# io-board-f-8.net
KiCad netlist of a schematic drawn in EAGLE
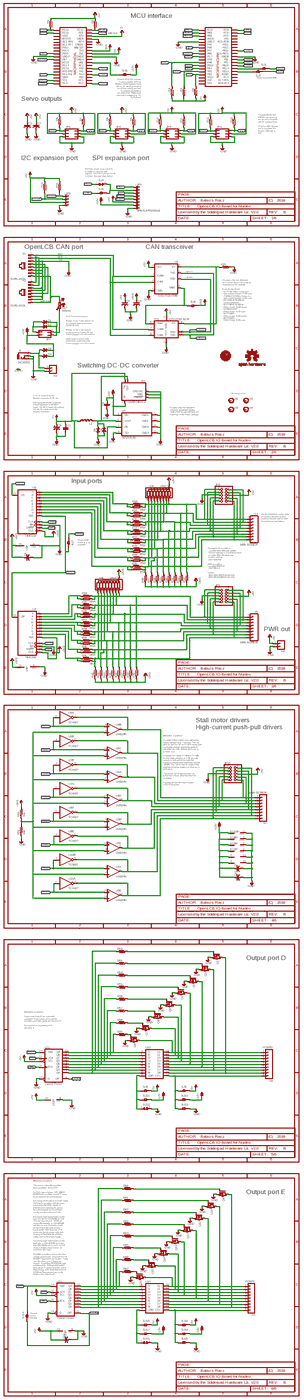
[diagram p0: schematic, sheet 1, overview]
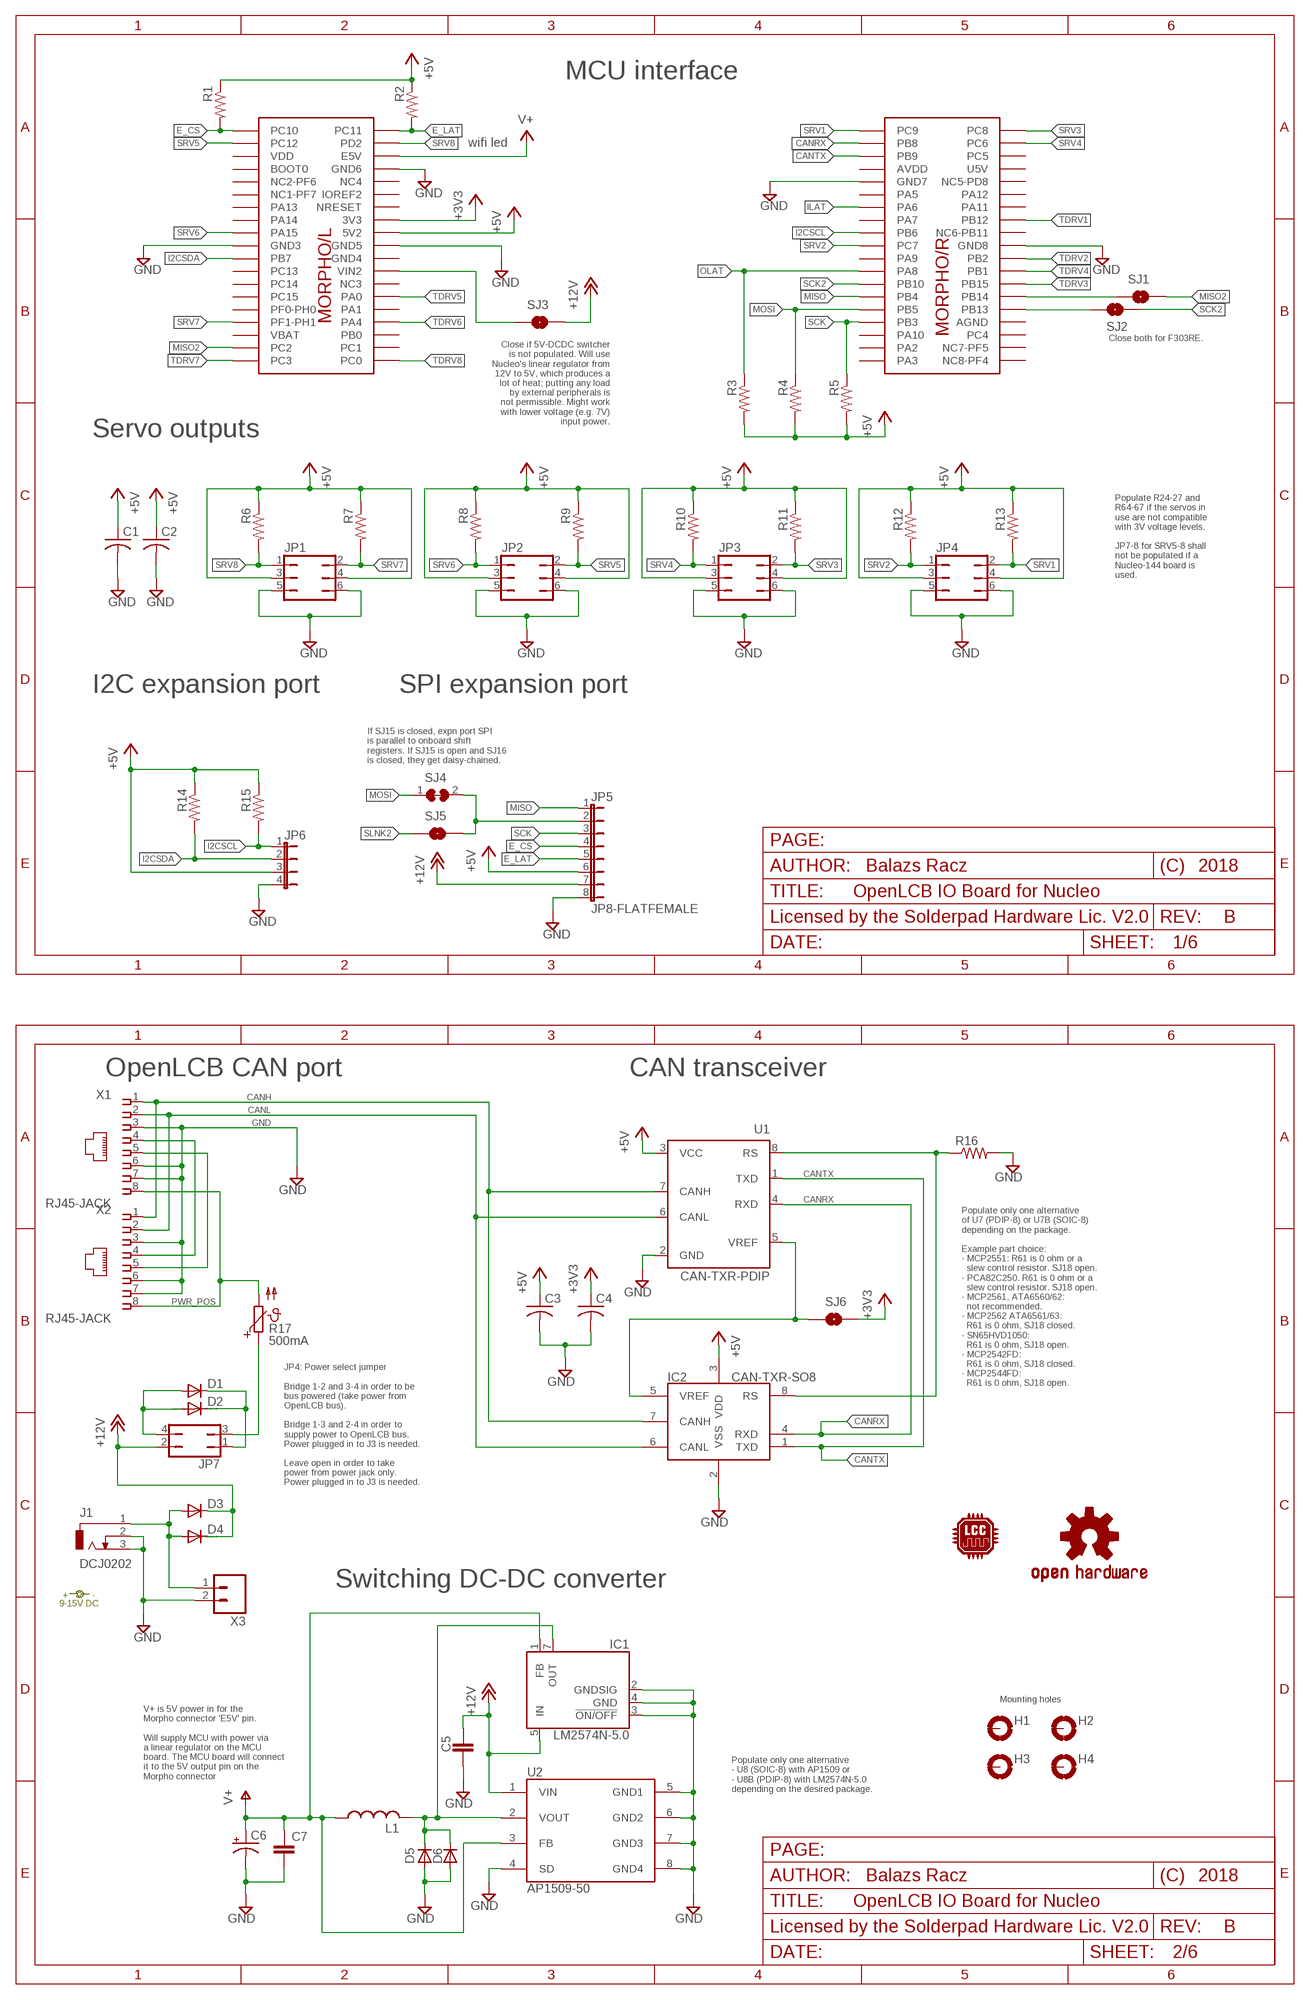
[diagram p1: schematic, sheet 1, part 1 of 4]
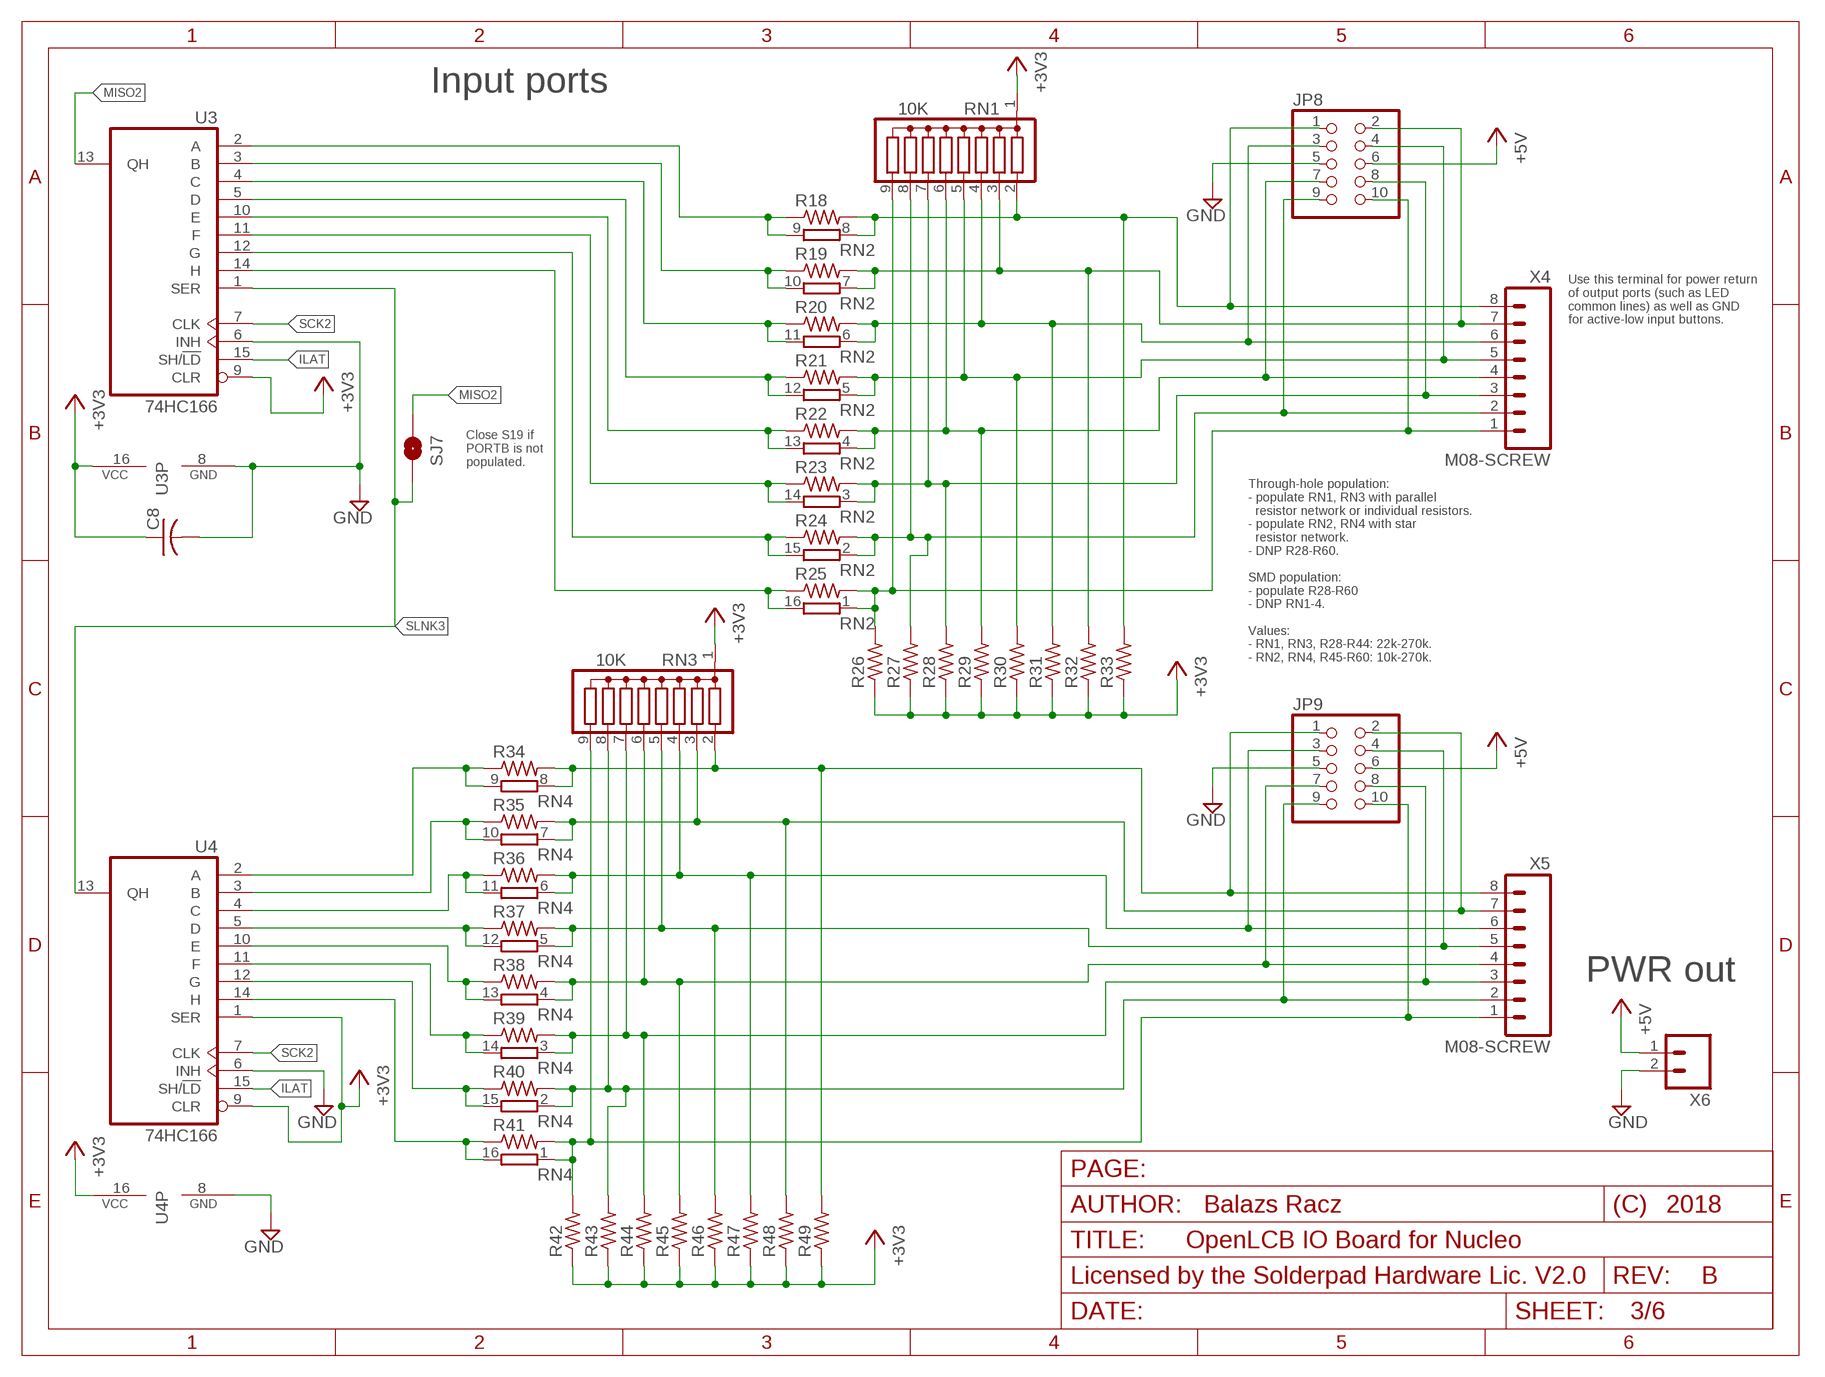
[diagram p2: schematic, sheet 1, part 2 of 4]
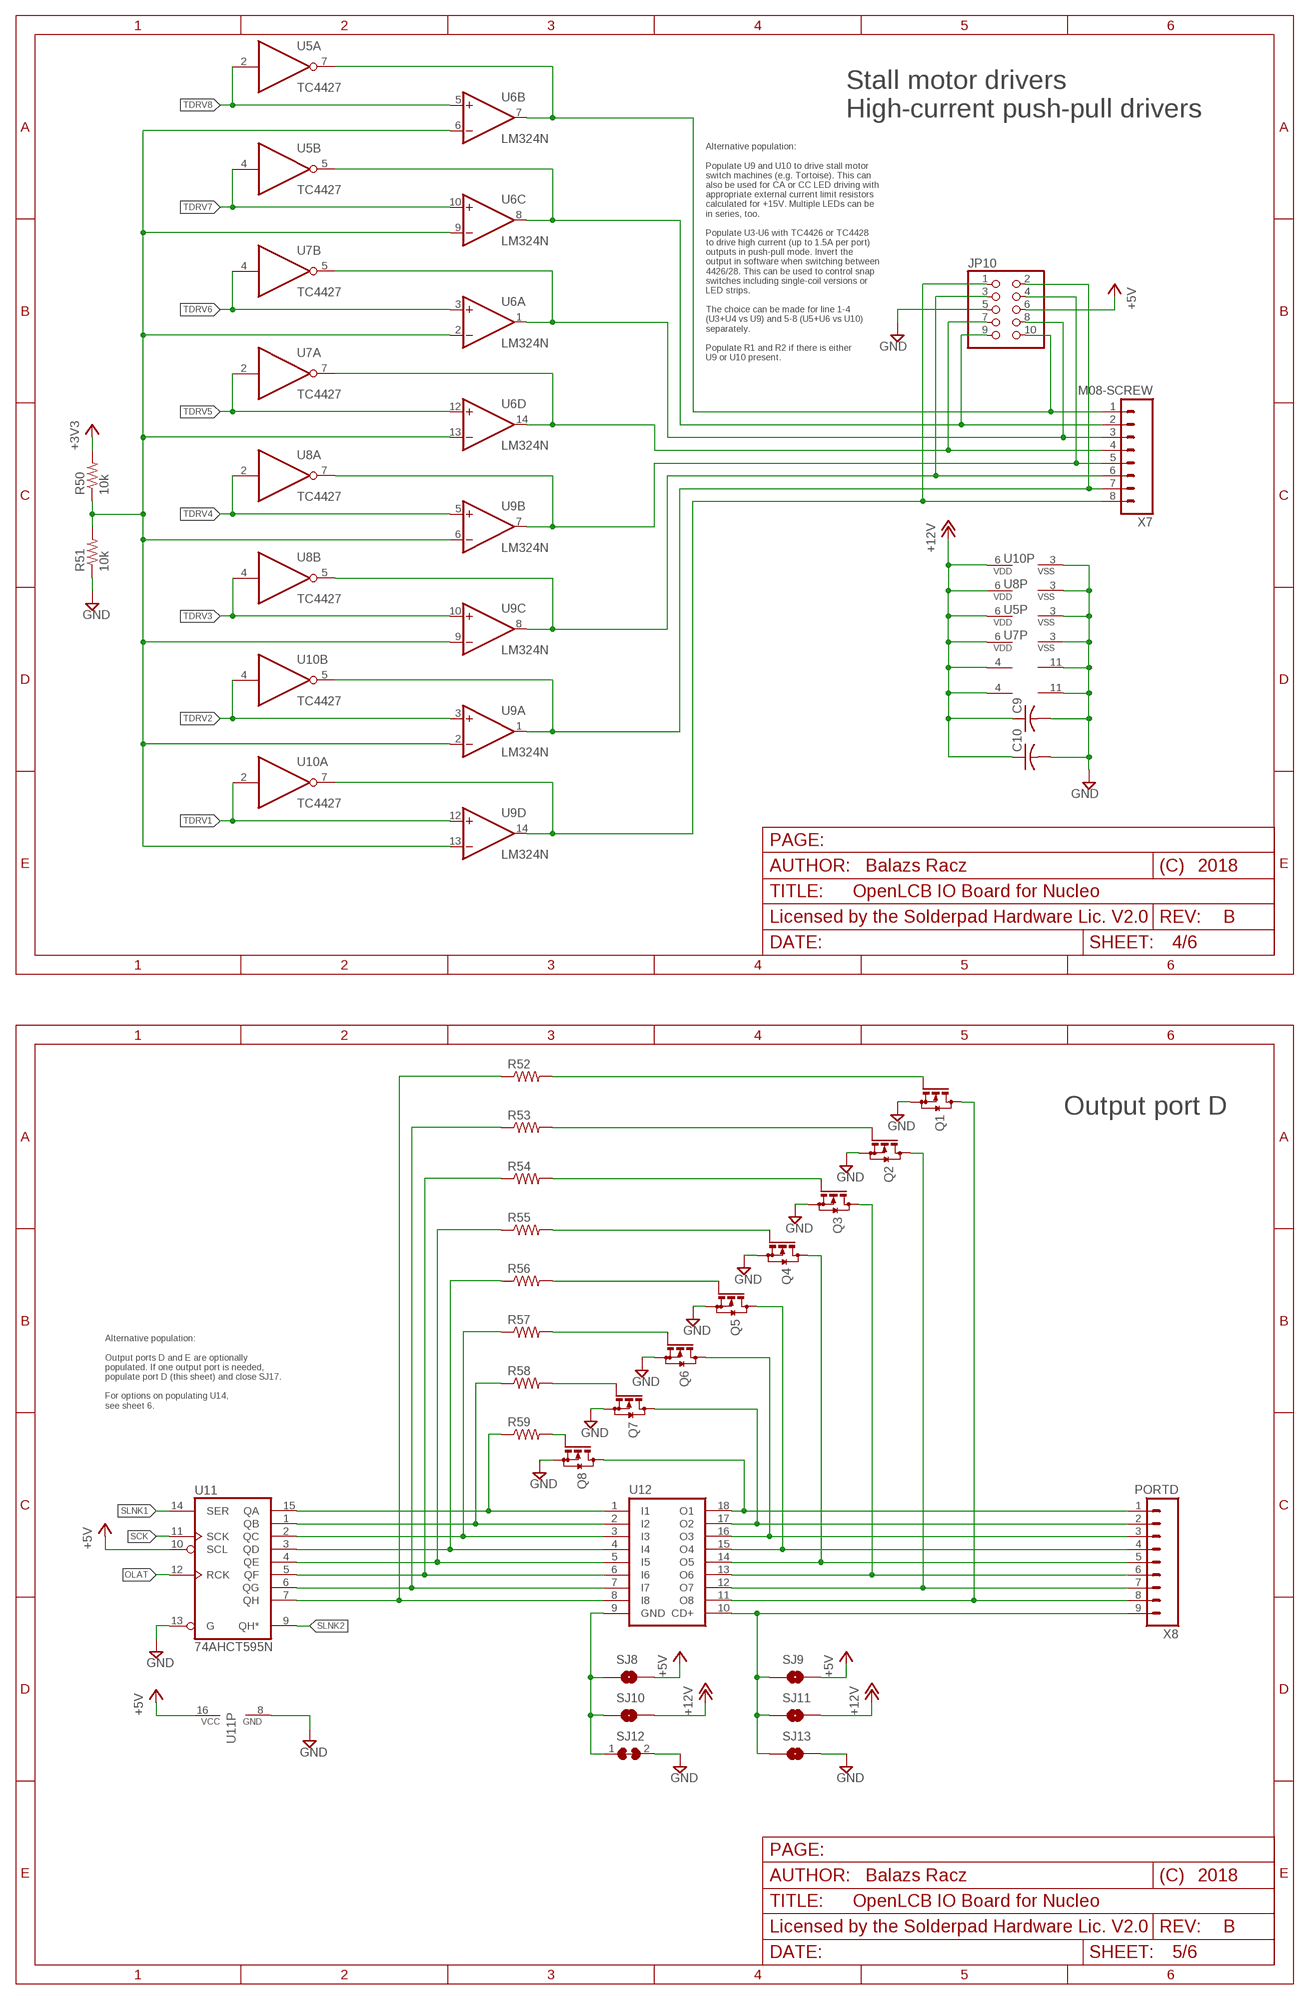
[diagram p3: schematic, sheet 1, part 3 of 4]
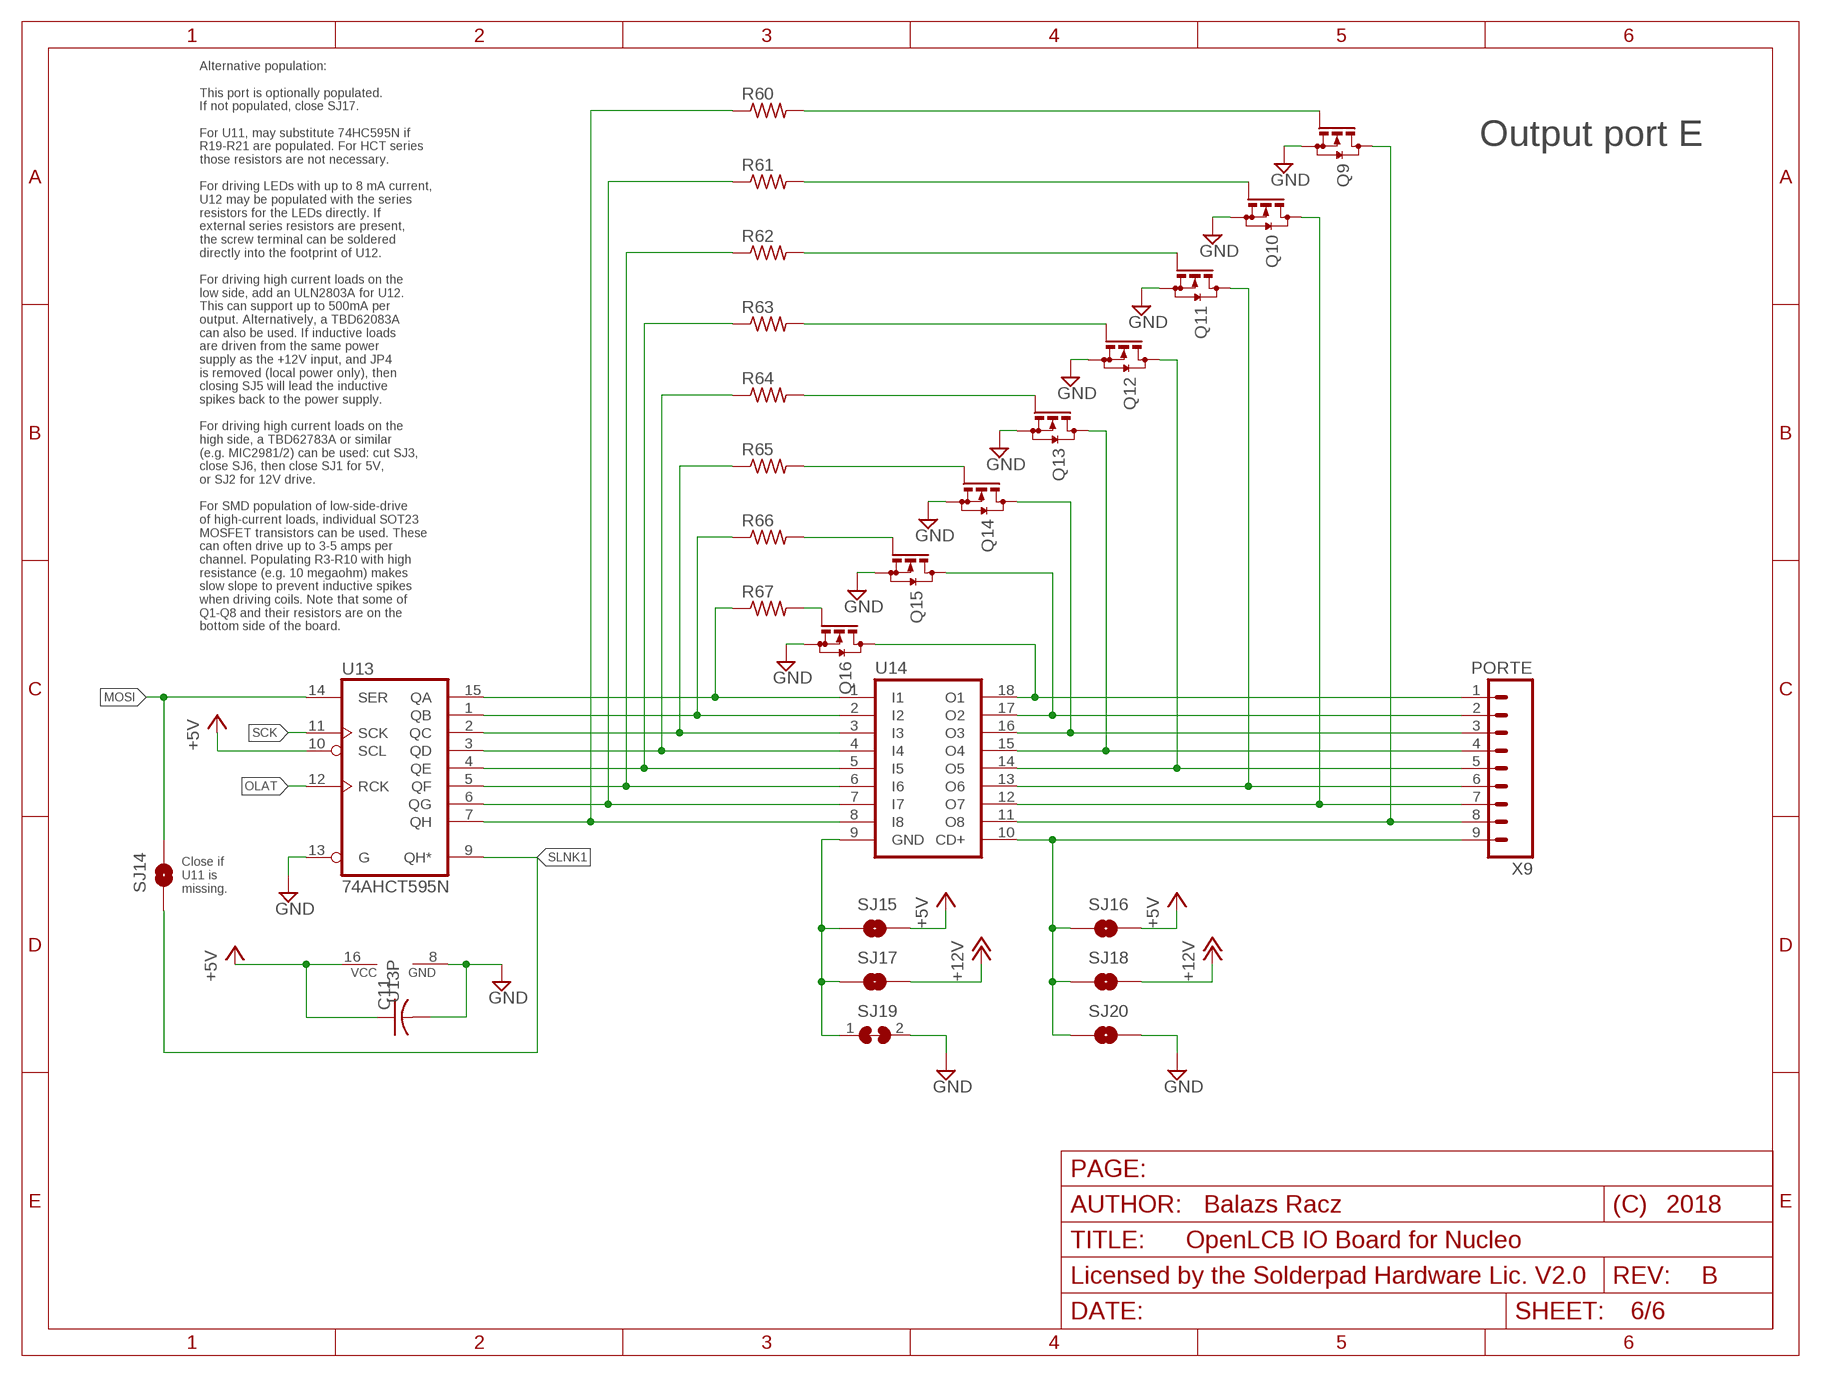
[diagram p4: schematic, sheet 1, part 4 of 4]

(export (version "E")
  (design (tool "Eeschema 10.0.6"))
  (components
    (comp (ref "C1")
      (value "C-USC1206")
      (footprint "eagle-import:C1206")
      (libsource (lib "eagle-import") (part "C-USC1206"))
    )
    (comp (ref "C2")
      (value "C-USC1206")
      (footprint "eagle-import:C1206")
      (libsource (lib "eagle-import") (part "C-USC1206"))
    )
    (comp (ref "C3")
      (value "C-USC0805")
      (footprint "eagle-import:C0805")
      (libsource (lib "eagle-import") (part "C-USC0805"))
    )
    (comp (ref "C4")
      (value "C-USC0805")
      (footprint "eagle-import:C0805")
      (libsource (lib "eagle-import") (part "C-USC0805"))
    )
    (comp (ref "C5")
      (value "C-EUC1206")
      (footprint "eagle-import:C1206")
      (libsource (lib "eagle-import") (part "C-EUC1206"))
    )
    (comp (ref "C6")
      (value "CPOL-USE2.5-5")
      (footprint "eagle-import:E2,5-5")
      (libsource (lib "eagle-import") (part "CPOL-USE2.5-5"))
    )
    (comp (ref "C7")
      (value "C-EUC1206")
      (footprint "eagle-import:C1206")
      (libsource (lib "eagle-import") (part "C-EUC1206"))
    )
    (comp (ref "C8")
      (value "C-USC0805")
      (footprint "eagle-import:C0805")
      (libsource (lib "eagle-import") (part "C-USC0805"))
    )
    (comp (ref "C9")
      (value "C-USC1206")
      (footprint "eagle-import:C1206")
      (libsource (lib "eagle-import") (part "C-USC1206"))
    )
    (comp (ref "C10")
      (value "C-USC1206")
      (footprint "eagle-import:C1206")
      (libsource (lib "eagle-import") (part "C-USC1206"))
    )
    (comp (ref "C11")
      (value "C-USC0805")
      (footprint "eagle-import:C0805")
      (libsource (lib "eagle-import") (part "C-USC0805"))
    )
    (comp (ref "D1")
      (value "DIODEDO-214AA-NODOC")
      (footprint "eagle-import:DO214AA-NODOC")
      (libsource (lib "eagle-import") (part "DIODEDO-214AA-NODOC"))
    )
    (comp (ref "D2")
      (value "DIODE-DO41-7.6")
      (footprint "eagle-import:DO41-7.6")
      (libsource (lib "eagle-import") (part "DIODE-DO41-7.6"))
    )
    (comp (ref "D3")
      (value "DIODEDO-214AA-NODOC")
      (footprint "eagle-import:DO214AA-NODOC")
      (libsource (lib "eagle-import") (part "DIODEDO-214AA-NODOC"))
    )
    (comp (ref "D4")
      (value "DIODE-DO41-7.6")
      (footprint "eagle-import:DO41-7.6")
      (libsource (lib "eagle-import") (part "DIODE-DO41-7.6"))
    )
    (comp (ref "D5")
      (value "DIODE-DO41-7.6")
      (footprint "eagle-import:DO41-7.6")
      (libsource (lib "eagle-import") (part "DIODE-DO41-7.6"))
    )
    (comp (ref "D6")
      (value "DIODEDO-214AA-NODOC")
      (footprint "eagle-import:DO214AA-NODOC")
      (libsource (lib "eagle-import") (part "DIODEDO-214AA-NODOC"))
    )
    (comp (ref "G1")
      (value "NUCLEO_64_GENERIC")
      (footprint "eagle-import:NUCLEO_BRD_BASE64")
      (libsource (lib "eagle-import") (part "NUCLEO_64_GENERIC"))
    )
    (comp (ref "H1")
      (value "MOUNT-PAD-ROUND3.3")
      (footprint "eagle-import:3,3-PAD")
      (libsource (lib "eagle-import") (part "MOUNT-PAD-ROUND3.3"))
    )
    (comp (ref "H2")
      (value "MOUNT-PAD-ROUND3.3")
      (footprint "eagle-import:3,3-PAD")
      (libsource (lib "eagle-import") (part "MOUNT-PAD-ROUND3.3"))
    )
    (comp (ref "H3")
      (value "MOUNT-PAD-ROUND3.3")
      (footprint "eagle-import:3,3-PAD")
      (libsource (lib "eagle-import") (part "MOUNT-PAD-ROUND3.3"))
    )
    (comp (ref "H4")
      (value "MOUNT-PAD-ROUND3.3")
      (footprint "eagle-import:3,3-PAD")
      (libsource (lib "eagle-import") (part "MOUNT-PAD-ROUND3.3"))
    )
    (comp (ref "IC1")
      (value "LM2574N-5.0")
      (footprint "eagle-import:DIL08")
      (libsource (lib "eagle-import") (part "LM2574?-N5.0"))
    )
    (comp (ref "IC2")
      (value "CAN-TXR-SO8")
      (footprint "eagle-import:SO-08")
      (libsource (lib "eagle-import") (part "MCP2551-SN"))
    )
    (comp (ref "J1")
      (value "DCJ0202")
      (footprint "eagle-import:DCJ0202")
      (libsource (lib "eagle-import") (part "DCJ0202"))
    )
    (comp (ref "JP1")
      (value "JP3Q")
      (footprint "eagle-import:JP3Q")
      (libsource (lib "eagle-import") (part "JP3Q"))
    )
    (comp (ref "JP2")
      (value "JP3Q")
      (footprint "eagle-import:JP3Q")
      (libsource (lib "eagle-import") (part "JP3Q"))
    )
    (comp (ref "JP3")
      (value "JP3Q")
      (footprint "eagle-import:JP3Q")
      (libsource (lib "eagle-import") (part "JP3Q"))
    )
    (comp (ref "JP4")
      (value "JP3Q")
      (footprint "eagle-import:JP3Q")
      (libsource (lib "eagle-import") (part "JP3Q"))
    )
    (comp (ref "JP5")
      (value "JP8-FLATFEMALE")
      (footprint "eagle-import:JP8F-FEM")
      (libsource (lib "eagle-import") (part "JP8-FLATFEMALE"))
    )
    (comp (ref "JP6")
      (value "JP4-FLAT")
      (footprint "eagle-import:JP4F")
      (libsource (lib "eagle-import") (part "JP4-FLAT"))
    )
    (comp (ref "JP7")
      (value "JP2Q")
      (footprint "eagle-import:JP2Q")
      (libsource (lib "eagle-import") (part "JP2Q"))
    )
    (comp (ref "JP8")
      (value "PINHD-2X5CN")
      (footprint "eagle-import:CON10M")
      (libsource (lib "eagle-import") (part "PINHD-2X5CN"))
    )
    (comp (ref "JP9")
      (value "PINHD-2X5CN")
      (footprint "eagle-import:CON10M")
      (libsource (lib "eagle-import") (part "PINHD-2X5CN"))
    )
    (comp (ref "JP10")
      (value "PINHD-2X5CN")
      (footprint "eagle-import:CON10M")
      (libsource (lib "eagle-import") (part "PINHD-2X5CN"))
    )
    (comp (ref "L1")
      (value "L-US")
      (footprint "eagle-import:L5-8,5")
      (libsource (lib "eagle-import") (part "L-US"))
    )
    (comp (ref "LG1")
      (value "LCC_LOGO")
      (footprint "eagle-import:LCC_LOGO")
      (libsource (lib "eagle-import") (part "LCC_LOGO"))
    )
    (comp (ref "LOGO1")
      (value "DOC-OSHW-LOGOM")
      (footprint "eagle-import:OSHW-LOGO-M")
      (libsource (lib "eagle-import") (part "DOC-OSHW-LOGOM"))
    )
    (comp (ref "P1")
      (value "9-15V DC")
      (footprint "eagle-import:POWER_USAGE")
      (libsource (lib "eagle-import") (part "DOC-POWER_LABEL"))
    )
    (comp (ref "Q1")
      (value "BSS123")
      (footprint "eagle-import:SOT23")
      (libsource (lib "eagle-import") (part "BSS123"))
    )
    (comp (ref "Q2")
      (value "BSS123")
      (footprint "eagle-import:SOT23")
      (libsource (lib "eagle-import") (part "BSS123"))
    )
    (comp (ref "Q3")
      (value "BSS123")
      (footprint "eagle-import:SOT23")
      (libsource (lib "eagle-import") (part "BSS123"))
    )
    (comp (ref "Q4")
      (value "BSS123")
      (footprint "eagle-import:SOT23")
      (libsource (lib "eagle-import") (part "BSS123"))
    )
    (comp (ref "Q5")
      (value "BSS123")
      (footprint "eagle-import:SOT23")
      (libsource (lib "eagle-import") (part "BSS123"))
    )
    (comp (ref "Q6")
      (value "BSS123")
      (footprint "eagle-import:SOT23")
      (libsource (lib "eagle-import") (part "BSS123"))
    )
    (comp (ref "Q7")
      (value "BSS123")
      (footprint "eagle-import:SOT23")
      (libsource (lib "eagle-import") (part "BSS123"))
    )
    (comp (ref "Q8")
      (value "BSS123")
      (footprint "eagle-import:SOT23")
      (libsource (lib "eagle-import") (part "BSS123"))
    )
    (comp (ref "Q9")
      (value "BSS123")
      (footprint "eagle-import:SOT23")
      (libsource (lib "eagle-import") (part "BSS123"))
    )
    (comp (ref "Q10")
      (value "BSS123")
      (footprint "eagle-import:SOT23")
      (libsource (lib "eagle-import") (part "BSS123"))
    )
    (comp (ref "Q11")
      (value "BSS123")
      (footprint "eagle-import:SOT23")
      (libsource (lib "eagle-import") (part "BSS123"))
    )
    (comp (ref "Q12")
      (value "BSS123")
      (footprint "eagle-import:SOT23")
      (libsource (lib "eagle-import") (part "BSS123"))
    )
    (comp (ref "Q13")
      (value "BSS123")
      (footprint "eagle-import:SOT23")
      (libsource (lib "eagle-import") (part "BSS123"))
    )
    (comp (ref "Q14")
      (value "BSS123")
      (footprint "eagle-import:SOT23")
      (libsource (lib "eagle-import") (part "BSS123"))
    )
    (comp (ref "Q15")
      (value "BSS123")
      (footprint "eagle-import:SOT23")
      (libsource (lib "eagle-import") (part "BSS123"))
    )
    (comp (ref "Q16")
      (value "BSS123")
      (footprint "eagle-import:SOT23")
      (libsource (lib "eagle-import") (part "BSS123"))
    )
    (comp (ref "R1")
      (value "R-US_R0805")
      (footprint "eagle-import:R0805")
      (libsource (lib "eagle-import") (part "rcl_334_R-US_R0805"))
    )
    (comp (ref "R2")
      (value "R-US_R0805")
      (footprint "eagle-import:R0805")
      (libsource (lib "eagle-import") (part "rcl_334_R-US_R0805"))
    )
    (comp (ref "R3")
      (value "R-US_R0805")
      (footprint "eagle-import:R0805")
      (libsource (lib "eagle-import") (part "rcl_334_R-US_R0805"))
    )
    (comp (ref "R4")
      (value "R-US_R0805")
      (footprint "eagle-import:R0805")
      (libsource (lib "eagle-import") (part "rcl_334_R-US_R0805"))
    )
    (comp (ref "R5")
      (value "R-US_R0805")
      (footprint "eagle-import:R0805")
      (libsource (lib "eagle-import") (part "rcl_334_R-US_R0805"))
    )
    (comp (ref "R6")
      (value "R-US_R0805")
      (footprint "eagle-import:R0805")
      (libsource (lib "eagle-import") (part "rcl_334_R-US_R0805"))
    )
    (comp (ref "R7")
      (value "R-US_R0805")
      (footprint "eagle-import:R0805")
      (libsource (lib "eagle-import") (part "rcl_334_R-US_R0805"))
    )
    (comp (ref "R8")
      (value "R-US_R0805")
      (footprint "eagle-import:R0805")
      (libsource (lib "eagle-import") (part "rcl_334_R-US_R0805"))
    )
    (comp (ref "R9")
      (value "R-US_R0805")
      (footprint "eagle-import:R0805")
      (libsource (lib "eagle-import") (part "rcl_334_R-US_R0805"))
    )
    (comp (ref "R10")
      (value "R-US_R0805")
      (footprint "eagle-import:R0805")
      (libsource (lib "eagle-import") (part "rcl_334_R-US_R0805"))
    )
    (comp (ref "R11")
      (value "R-US_R0805")
      (footprint "eagle-import:R0805")
      (libsource (lib "eagle-import") (part "rcl_334_R-US_R0805"))
    )
    (comp (ref "R12")
      (value "R-US_R0805")
      (footprint "eagle-import:R0805")
      (libsource (lib "eagle-import") (part "rcl_334_R-US_R0805"))
    )
    (comp (ref "R13")
      (value "R-US_R0805")
      (footprint "eagle-import:R0805")
      (libsource (lib "eagle-import") (part "rcl_334_R-US_R0805"))
    )
    (comp (ref "R14")
      (value "R-US_R0805")
      (footprint "eagle-import:R0805")
      (libsource (lib "eagle-import") (part "rcl_334_R-US_R0805"))
    )
    (comp (ref "R15")
      (value "R-US_R0805")
      (footprint "eagle-import:R0805")
      (libsource (lib "eagle-import") (part "rcl_334_R-US_R0805"))
    )
    (comp (ref "R16")
      (value "R-US_R0805")
      (footprint "eagle-import:R0805")
      (libsource (lib "eagle-import") (part "rcl_334_R-US_R0805"))
    )
    (comp (ref "R17")
      (value "500mA")
      (footprint "eagle-import:PTC1812")
      (libsource (lib "eagle-import") (part "PTC_1812"))
    )
    (comp (ref "R18")
      (value "R-US_R0603")
      (footprint "eagle-import:R0603")
      (libsource (lib "eagle-import") (part "rcl_334_R-US_R0603"))
    )
    (comp (ref "R19")
      (value "R-US_R0603")
      (footprint "eagle-import:R0603")
      (libsource (lib "eagle-import") (part "rcl_334_R-US_R0603"))
    )
    (comp (ref "R20")
      (value "R-US_R0603")
      (footprint "eagle-import:R0603")
      (libsource (lib "eagle-import") (part "rcl_334_R-US_R0603"))
    )
    (comp (ref "R21")
      (value "R-US_R0603")
      (footprint "eagle-import:R0603")
      (libsource (lib "eagle-import") (part "rcl_334_R-US_R0603"))
    )
    (comp (ref "R22")
      (value "R-US_R0603")
      (footprint "eagle-import:R0603")
      (libsource (lib "eagle-import") (part "rcl_334_R-US_R0603"))
    )
    (comp (ref "R23")
      (value "R-US_R0603")
      (footprint "eagle-import:R0603")
      (libsource (lib "eagle-import") (part "rcl_334_R-US_R0603"))
    )
    (comp (ref "R24")
      (value "R-US_R0603")
      (footprint "eagle-import:R0603")
      (libsource (lib "eagle-import") (part "rcl_334_R-US_R0603"))
    )
    (comp (ref "R25")
      (value "R-US_R0603")
      (footprint "eagle-import:R0603")
      (libsource (lib "eagle-import") (part "rcl_334_R-US_R0603"))
    )
    (comp (ref "R26")
      (value "R-US")
      (footprint "eagle-import:R0603")
      (libsource (lib "eagle-import") (part "R-US"))
    )
    (comp (ref "R27")
      (value "R-US")
      (footprint "eagle-import:R0603")
      (libsource (lib "eagle-import") (part "R-US"))
    )
    (comp (ref "R28")
      (value "R-US")
      (footprint "eagle-import:R0603")
      (libsource (lib "eagle-import") (part "R-US"))
    )
    (comp (ref "R29")
      (value "R-US")
      (footprint "eagle-import:R0603")
      (libsource (lib "eagle-import") (part "R-US"))
    )
    (comp (ref "R30")
      (value "R-US")
      (footprint "eagle-import:R0603")
      (libsource (lib "eagle-import") (part "R-US"))
    )
    (comp (ref "R31")
      (value "R-US")
      (footprint "eagle-import:R0603")
      (libsource (lib "eagle-import") (part "R-US"))
    )
    (comp (ref "R32")
      (value "R-US")
      (footprint "eagle-import:R0603")
      (libsource (lib "eagle-import") (part "R-US"))
    )
    (comp (ref "R33")
      (value "R-US")
      (footprint "eagle-import:R0603")
      (libsource (lib "eagle-import") (part "R-US"))
    )
    (comp (ref "R34")
      (value "R-US_R0603")
      (footprint "eagle-import:R0603")
      (libsource (lib "eagle-import") (part "rcl_334_R-US_R0603"))
    )
    (comp (ref "R35")
      (value "R-US_R0603")
      (footprint "eagle-import:R0603")
      (libsource (lib "eagle-import") (part "rcl_334_R-US_R0603"))
    )
    (comp (ref "R36")
      (value "R-US_R0603")
      (footprint "eagle-import:R0603")
      (libsource (lib "eagle-import") (part "rcl_334_R-US_R0603"))
    )
    (comp (ref "R37")
      (value "R-US_R0603")
      (footprint "eagle-import:R0603")
      (libsource (lib "eagle-import") (part "rcl_334_R-US_R0603"))
    )
    (comp (ref "R38")
      (value "R-US_R0603")
      (footprint "eagle-import:R0603")
      (libsource (lib "eagle-import") (part "rcl_334_R-US_R0603"))
    )
    (comp (ref "R39")
      (value "R-US_R0603")
      (footprint "eagle-import:R0603")
      (libsource (lib "eagle-import") (part "rcl_334_R-US_R0603"))
    )
    (comp (ref "R40")
      (value "R-US_R0603")
      (footprint "eagle-import:R0603")
      (libsource (lib "eagle-import") (part "rcl_334_R-US_R0603"))
    )
    (comp (ref "R41")
      (value "R-US_R0603")
      (footprint "eagle-import:R0603")
      (libsource (lib "eagle-import") (part "rcl_334_R-US_R0603"))
    )
    (comp (ref "R42")
      (value "R-US")
      (footprint "eagle-import:R0603")
      (libsource (lib "eagle-import") (part "R-US"))
    )
    (comp (ref "R43")
      (value "R-US")
      (footprint "eagle-import:R0603")
      (libsource (lib "eagle-import") (part "R-US"))
    )
    (comp (ref "R44")
      (value "R-US")
      (footprint "eagle-import:R0603")
      (libsource (lib "eagle-import") (part "R-US"))
    )
    (comp (ref "R45")
      (value "R-US")
      (footprint "eagle-import:R0603")
      (libsource (lib "eagle-import") (part "R-US"))
    )
    (comp (ref "R46")
      (value "R-US")
      (footprint "eagle-import:R0603")
      (libsource (lib "eagle-import") (part "R-US"))
    )
    (comp (ref "R47")
      (value "R-US")
      (footprint "eagle-import:R0603")
      (libsource (lib "eagle-import") (part "R-US"))
    )
    (comp (ref "R48")
      (value "R-US")
      (footprint "eagle-import:R0603")
      (libsource (lib "eagle-import") (part "R-US"))
    )
    (comp (ref "R49")
      (value "R-US")
      (footprint "eagle-import:R0603")
      (libsource (lib "eagle-import") (part "R-US"))
    )
    (comp (ref "R50")
      (value "10k")
      (footprint "eagle-import:R0805")
      (libsource (lib "eagle-import") (part "R-US_R0805"))
    )
    (comp (ref "R51")
      (value "10k")
      (footprint "eagle-import:R0805")
      (libsource (lib "eagle-import") (part "R-US_R0805"))
    )
    (comp (ref "R52")
      (value "R-US_R0603")
      (footprint "eagle-import:R0603")
      (libsource (lib "eagle-import") (part "R-US_R0603"))
    )
    (comp (ref "R53")
      (value "R-US_R0603")
      (footprint "eagle-import:R0603")
      (libsource (lib "eagle-import") (part "R-US_R0603"))
    )
    (comp (ref "R54")
      (value "R-US_R0603")
      (footprint "eagle-import:R0603")
      (libsource (lib "eagle-import") (part "R-US_R0603"))
    )
    (comp (ref "R55")
      (value "R-US_R0603")
      (footprint "eagle-import:R0603")
      (libsource (lib "eagle-import") (part "R-US_R0603"))
    )
    (comp (ref "R56")
      (value "R-US_R0603")
      (footprint "eagle-import:R0603")
      (libsource (lib "eagle-import") (part "R-US_R0603"))
    )
    (comp (ref "R57")
      (value "R-US_R0603")
      (footprint "eagle-import:R0603")
      (libsource (lib "eagle-import") (part "R-US_R0603"))
    )
    (comp (ref "R58")
      (value "R-US_R0603")
      (footprint "eagle-import:R0603")
      (libsource (lib "eagle-import") (part "R-US_R0603"))
    )
    (comp (ref "R59")
      (value "R-US_R0603")
      (footprint "eagle-import:R0603")
      (libsource (lib "eagle-import") (part "R-US_R0603"))
    )
    (comp (ref "R60")
      (value "R-US_R0603")
      (footprint "eagle-import:R0603")
      (libsource (lib "eagle-import") (part "R-US_R0603"))
    )
    (comp (ref "R61")
      (value "R-US_R0603")
      (footprint "eagle-import:R0603")
      (libsource (lib "eagle-import") (part "R-US_R0603"))
    )
    (comp (ref "R62")
      (value "R-US_R0603")
      (footprint "eagle-import:R0603")
      (libsource (lib "eagle-import") (part "R-US_R0603"))
    )
    (comp (ref "R63")
      (value "R-US_R0603")
      (footprint "eagle-import:R0603")
      (libsource (lib "eagle-import") (part "R-US_R0603"))
    )
    (comp (ref "R64")
      (value "R-US_R0603")
      (footprint "eagle-import:R0603")
      (libsource (lib "eagle-import") (part "R-US_R0603"))
    )
    (comp (ref "R65")
      (value "R-US_R0603")
      (footprint "eagle-import:R0603")
      (libsource (lib "eagle-import") (part "R-US_R0603"))
    )
    (comp (ref "R66")
      (value "R-US_R0603")
      (footprint "eagle-import:R0603")
      (libsource (lib "eagle-import") (part "R-US_R0603"))
    )
    (comp (ref "R67")
      (value "R-US_R0603")
      (footprint "eagle-import:R0603")
      (libsource (lib "eagle-import") (part "R-US_R0603"))
    )
    (comp (ref "RN1")
      (value "10K")
      (footprint "eagle-import:SIL9")
      (libsource (lib "eagle-import") (part "G08R"))
    )
    (comp (ref "RN2")
      (value "8R-P")
      (footprint "eagle-import:DIL16")
      (libsource (lib "eagle-import") (part "8R-P"))
    )
    (comp (ref "RN3")
      (value "10K")
      (footprint "eagle-import:SIL9")
      (libsource (lib "eagle-import") (part "G08R"))
    )
    (comp (ref "RN4")
      (value "8R-P")
      (footprint "eagle-import:DIL16")
      (libsource (lib "eagle-import") (part "8R-P"))
    )
    (comp (ref "SJ1")
      (value "SJRND2")
      (footprint "eagle-import:SJ_RND2")
      (libsource (lib "eagle-import") (part "SJRND2"))
    )
    (comp (ref "SJ2")
      (value "SJRND2")
      (footprint "eagle-import:SJ_RND2")
      (libsource (lib "eagle-import") (part "SJRND2"))
    )
    (comp (ref "SJ3")
      (value "SJRND2")
      (footprint "eagle-import:SJ_RND2")
      (libsource (lib "eagle-import") (part "SJRND2"))
    )
    (comp (ref "SJ4")
      (value "SJ-C")
      (footprint "eagle-import:SJW-C")
      (libsource (lib "eagle-import") (part "SJ-C"))
    )
    (comp (ref "SJ5")
      (value "SJRND2")
      (footprint "eagle-import:SJ_RND2")
      (libsource (lib "eagle-import") (part "SJRND2"))
    )
    (comp (ref "SJ6")
      (value "SJRND2")
      (footprint "eagle-import:SJ_RND2")
      (libsource (lib "eagle-import") (part "SJRND2"))
    )
    (comp (ref "SJ7")
      (value "SJRND2")
      (footprint "eagle-import:SJ_RND2")
      (libsource (lib "eagle-import") (part "SJRND2"))
    )
    (comp (ref "SJ8")
      (value "SJRND2")
      (footprint "eagle-import:SJ_RND2")
      (libsource (lib "eagle-import") (part "SJRND2"))
    )
    (comp (ref "SJ9")
      (value "SJRND2")
      (footprint "eagle-import:SJ_RND2")
      (libsource (lib "eagle-import") (part "SJRND2"))
    )
    (comp (ref "SJ10")
      (value "SJRND2")
      (footprint "eagle-import:SJ_RND2")
      (libsource (lib "eagle-import") (part "SJRND2"))
    )
    (comp (ref "SJ11")
      (value "SJRND2")
      (footprint "eagle-import:SJ_RND2")
      (libsource (lib "eagle-import") (part "SJRND2"))
    )
    (comp (ref "SJ12")
      (value "SJ-C")
      (footprint "eagle-import:SJW-C")
      (libsource (lib "eagle-import") (part "SJ-C"))
    )
    (comp (ref "SJ13")
      (value "SJRND2")
      (footprint "eagle-import:SJ_RND2")
      (libsource (lib "eagle-import") (part "SJRND2"))
    )
    (comp (ref "SJ14")
      (value "SJRND2")
      (footprint "eagle-import:SJ_RND2")
      (libsource (lib "eagle-import") (part "SJRND2"))
    )
    (comp (ref "SJ15")
      (value "SJRND2")
      (footprint "eagle-import:SJ_RND2")
      (libsource (lib "eagle-import") (part "SJRND2"))
    )
    (comp (ref "SJ16")
      (value "SJRND2")
      (footprint "eagle-import:SJ_RND2")
      (libsource (lib "eagle-import") (part "SJRND2"))
    )
    (comp (ref "SJ17")
      (value "SJRND2")
      (footprint "eagle-import:SJ_RND2")
      (libsource (lib "eagle-import") (part "SJRND2"))
    )
    (comp (ref "SJ18")
      (value "SJRND2")
      (footprint "eagle-import:SJ_RND2")
      (libsource (lib "eagle-import") (part "SJRND2"))
    )
    (comp (ref "SJ19")
      (value "SJ-C")
      (footprint "eagle-import:SJW-C")
      (libsource (lib "eagle-import") (part "SJ-C"))
    )
    (comp (ref "SJ20")
      (value "SJRND2")
      (footprint "eagle-import:SJ_RND2")
      (libsource (lib "eagle-import") (part "SJRND2"))
    )
    (comp (ref "U1")
      (value "CAN-TXR-PDIP")
      (footprint "eagle-import:DIL08")
      (libsource (lib "eagle-import") (part "PCA82C250"))
    )
    (comp (ref "U2")
      (value "AP1509-50")
      (footprint "eagle-import:SO-08")
      (libsource (lib "eagle-import") (part "AP1509"))
    )
    (comp (ref "U3")
      (value "74HC166")
      (footprint "eagle-import:DIL16")
      (libsource (lib "eagle-import") (part "74166N"))
    )
    (comp (ref "U4")
      (value "74HC166")
      (footprint "eagle-import:DIL16")
      (libsource (lib "eagle-import") (part "74166N"))
    )
    (comp (ref "U5")
      (value "TC4427")
      (footprint "eagle-import:DIL08-LONG")
      (libsource (lib "eagle-import") (part "TC4426APDIP"))
    )
    (comp (ref "U6")
      (value "LM324N")
      (footprint "eagle-import:DIL14")
      (libsource (lib "eagle-import") (part "LM324N"))
    )
    (comp (ref "U7")
      (value "TC4427")
      (footprint "eagle-import:DIL08-LONG")
      (libsource (lib "eagle-import") (part "TC4426APDIP"))
    )
    (comp (ref "U8")
      (value "TC4427")
      (footprint "eagle-import:DIL08-LONG")
      (libsource (lib "eagle-import") (part "TC4426APDIP"))
    )
    (comp (ref "U9")
      (value "LM324N")
      (footprint "eagle-import:DIL14")
      (libsource (lib "eagle-import") (part "LM324N"))
    )
    (comp (ref "U10")
      (value "TC4427")
      (footprint "eagle-import:DIL08-LONG")
      (libsource (lib "eagle-import") (part "TC4426APDIP"))
    )
    (comp (ref "U11")
      (value "74AHCT595N")
      (footprint "eagle-import:DIL16")
      (libsource (lib "eagle-import") (part "74595NHCT"))
    )
    (comp (ref "U12")
      (value "ULN2803A")
      (footprint "eagle-import:DIL18-THIN")
      (libsource (lib "eagle-import") (part "ULN2803A"))
    )
    (comp (ref "U13")
      (value "74AHCT595N")
      (footprint "eagle-import:DIL16")
      (libsource (lib "eagle-import") (part "74595NHCT"))
    )
    (comp (ref "U14")
      (value "ULN2803A")
      (footprint "eagle-import:DIL18-THIN")
      (libsource (lib "eagle-import") (part "ULN2803A"))
    )
    (comp (ref "X1")
      (value "RJ45-JACK")
      (footprint "eagle-import:RJ45-PULSE-E5J88")
      (libsource (lib "eagle-import") (part "RJ45-JACKRJ45-PULSE-E5J00"))
    )
    (comp (ref "X2")
      (value "RJ45-JACK")
      (footprint "eagle-import:RJ45-PULSE-E5J88")
      (libsource (lib "eagle-import") (part "RJ45-JACKRJ45-PULSE-E5J00"))
    )
    (comp (ref "X3")
      (value "CONNECTOR-M023.5MM-LOCK")
      (footprint "eagle-import:SCREWTERMINAL-3.5MM-2_LOCK")
      (libsource (lib "eagle-import") (part "CONNECTOR-M023.5MM-LOCK"))
    )
    (comp (ref "X4")
      (value "M08-SCREW")
      (footprint "eagle-import:1X08_TERMINAL")
      (libsource (lib "eagle-import") (part "M08-SCREW"))
    )
    (comp (ref "X5")
      (value "M08-SCREW")
      (footprint "eagle-import:1X08_TERMINAL")
      (libsource (lib "eagle-import") (part "M08-SCREW"))
    )
    (comp (ref "X6")
      (value "CONNECTOR-M023.5MM-LOCK")
      (footprint "eagle-import:SCREWTERMINAL-3.5MM-2_LOCK")
      (libsource (lib "eagle-import") (part "CONNECTOR-M023.5MM-LOCK"))
    )
    (comp (ref "X7")
      (value "M08-SCREW")
      (footprint "eagle-import:1X08_TERMINAL")
      (libsource (lib "eagle-import") (part "M08-SCREW"))
    )
    (comp (ref "X8")
      (value "PORTD")
      (footprint "eagle-import:1X09_TERMINAL")
      (libsource (lib "eagle-import") (part "M09-SCREW"))
    )
    (comp (ref "X9")
      (value "PORTE")
      (footprint "eagle-import:1X09_TERMINAL")
      (libsource (lib "eagle-import") (part "M09-SCREW"))
    )
  )
  (nets
    (net (code "1") (name "+3V3") (class "Default")
      (node (ref "C4") (pin "1") (pinfunction "1_1") (pintype "passive"))
      (node (ref "C8") (pin "1") (pinfunction "1_1") (pintype "passive"))
      (node (ref "G1") (pin "3V3") (pinfunction "3V3_3V3") (pintype "power_in"))
      (node (ref "R26") (pin "1") (pinfunction "1_1") (pintype "passive"))
      (node (ref "R27") (pin "1") (pinfunction "1_1") (pintype "passive"))
      (node (ref "R28") (pin "1") (pinfunction "1_1") (pintype "passive"))
      (node (ref "R29") (pin "1") (pinfunction "1_1") (pintype "passive"))
      (node (ref "R30") (pin "1") (pinfunction "1_1") (pintype "passive"))
      (node (ref "R31") (pin "1") (pinfunction "1_1") (pintype "passive"))
      (node (ref "R32") (pin "1") (pinfunction "1_1") (pintype "passive"))
      (node (ref "R33") (pin "1") (pinfunction "1_1") (pintype "passive"))
      (node (ref "R42") (pin "1") (pinfunction "1_1") (pintype "passive"))
      (node (ref "R43") (pin "1") (pinfunction "1_1") (pintype "passive"))
      (node (ref "R44") (pin "1") (pinfunction "1_1") (pintype "passive"))
      (node (ref "R45") (pin "1") (pinfunction "1_1") (pintype "passive"))
      (node (ref "R46") (pin "1") (pinfunction "1_1") (pintype "passive"))
      (node (ref "R47") (pin "1") (pinfunction "1_1") (pintype "passive"))
      (node (ref "R48") (pin "1") (pinfunction "1_1") (pintype "passive"))
      (node (ref "R49") (pin "1") (pinfunction "1_1") (pintype "passive"))
      (node (ref "R50") (pin "2") (pinfunction "2_2") (pintype "passive"))
      (node (ref "RN1") (pin "1") (pinfunction "1_1") (pintype "passive"))
      (node (ref "RN3") (pin "1") (pinfunction "1_1") (pintype "passive"))
      (node (ref "SJ6") (pin "P$1") (pinfunction "1_P$1") (pintype "passive"))
      (node (ref "U3") (pin "16") (pinfunction "VCC_16") (pintype "power_in"))
      (node (ref "U3") (pin "9") (pinfunction "CLR_9") (pintype "input"))
      (node (ref "U4") (pin "1") (pinfunction "SER_1") (pintype "input"))
      (node (ref "U4") (pin "16") (pinfunction "VCC_16") (pintype "power_in"))
      (node (ref "U4") (pin "9") (pinfunction "CLR_9") (pintype "input"))
    )
    (net (code "2") (name "+5V") (class "Default")
      (node (ref "C1") (pin "1") (pinfunction "1_1") (pintype "passive"))
      (node (ref "C11") (pin "1") (pinfunction "1_1") (pintype "passive"))
      (node (ref "C2") (pin "1") (pinfunction "1_1") (pintype "passive"))
      (node (ref "C3") (pin "1") (pinfunction "1_1") (pintype "passive"))
      (node (ref "G1") (pin "5V2") (pinfunction "5V2_5V2") (pintype "power_in"))
      (node (ref "IC2") (pin "3") (pinfunction "VDD_3") (pintype "power_in"))
      (node (ref "JP1") (pin "3") (pinfunction "3_3") (pintype "passive"))
      (node (ref "JP1") (pin "4") (pinfunction "4_4") (pintype "passive"))
      (node (ref "JP10") (pin "6") (pinfunction "6_6") (pintype "passive"))
      (node (ref "JP2") (pin "3") (pinfunction "3_3") (pintype "passive"))
      (node (ref "JP2") (pin "4") (pinfunction "4_4") (pintype "passive"))
      (node (ref "JP3") (pin "3") (pinfunction "3_3") (pintype "passive"))
      (node (ref "JP3") (pin "4") (pinfunction "4_4") (pintype "passive"))
      (node (ref "JP4") (pin "3") (pinfunction "3_3") (pintype "passive"))
      (node (ref "JP4") (pin "4") (pinfunction "4_4") (pintype "passive"))
      (node (ref "JP5") (pin "6") (pinfunction "6_6") (pintype "passive"))
      (node (ref "JP6") (pin "3") (pinfunction "3_3") (pintype "passive"))
      (node (ref "JP8") (pin "6") (pinfunction "6_6") (pintype "passive"))
      (node (ref "JP9") (pin "6") (pinfunction "6_6") (pintype "passive"))
      (node (ref "R1") (pin "1") (pinfunction "1_1") (pintype "passive"))
      (node (ref "R10") (pin "1") (pinfunction "1_1") (pintype "passive"))
      (node (ref "R11") (pin "1") (pinfunction "1_1") (pintype "passive"))
      (node (ref "R12") (pin "1") (pinfunction "1_1") (pintype "passive"))
      (node (ref "R13") (pin "1") (pinfunction "1_1") (pintype "passive"))
      (node (ref "R14") (pin "1") (pinfunction "1_1") (pintype "passive"))
      (node (ref "R15") (pin "1") (pinfunction "1_1") (pintype "passive"))
      (node (ref "R2") (pin "1") (pinfunction "1_1") (pintype "passive"))
      (node (ref "R3") (pin "2") (pinfunction "2_2") (pintype "passive"))
      (node (ref "R4") (pin "2") (pinfunction "2_2") (pintype "passive"))
      (node (ref "R5") (pin "2") (pinfunction "2_2") (pintype "passive"))
      (node (ref "R6") (pin "1") (pinfunction "1_1") (pintype "passive"))
      (node (ref "R7") (pin "1") (pinfunction "1_1") (pintype "passive"))
      (node (ref "R8") (pin "1") (pinfunction "1_1") (pintype "passive"))
      (node (ref "R9") (pin "1") (pinfunction "1_1") (pintype "passive"))
      (node (ref "SJ15") (pin "P$2") (pinfunction "2_P$2") (pintype "passive"))
      (node (ref "SJ16") (pin "P$2") (pinfunction "2_P$2") (pintype "passive"))
      (node (ref "SJ8") (pin "P$2") (pinfunction "2_P$2") (pintype "passive"))
      (node (ref "SJ9") (pin "P$2") (pinfunction "2_P$2") (pintype "passive"))
      (node (ref "U1") (pin "3") (pinfunction "VCC_3") (pintype "power_in"))
      (node (ref "U11") (pin "10") (pinfunction "SCL_10") (pintype "input"))
      (node (ref "U11") (pin "16") (pinfunction "VCC_16") (pintype "power_in"))
      (node (ref "U13") (pin "10") (pinfunction "SCL_10") (pintype "input"))
      (node (ref "U13") (pin "16") (pinfunction "VCC_16") (pintype "power_in"))
      (node (ref "X6") (pin "1") (pinfunction "1_1") (pintype "passive"))
    )
    (net (code "3") (name "+12V") (class "Default")
      (node (ref "C10") (pin "1") (pinfunction "1_1") (pintype "passive"))
      (node (ref "C5") (pin "1") (pinfunction "1_1") (pintype "passive"))
      (node (ref "C9") (pin "1") (pinfunction "1_1") (pintype "passive"))
      (node (ref "D3") (pin "C") (pinfunction "C_C") (pintype "passive"))
      (node (ref "D4") (pin "C") (pinfunction "C_C") (pintype "passive"))
      (node (ref "IC1") (pin "5") (pinfunction "IN_5") (pintype "input"))
      (node (ref "JP5") (pin "7") (pinfunction "7_7") (pintype "passive"))
      (node (ref "JP7") (pin "2") (pinfunction "2_2") (pintype "passive"))
      (node (ref "SJ10") (pin "P$2") (pinfunction "2_P$2") (pintype "passive"))
      (node (ref "SJ11") (pin "P$2") (pinfunction "2_P$2") (pintype "passive"))
      (node (ref "SJ17") (pin "P$2") (pinfunction "2_P$2") (pintype "passive"))
      (node (ref "SJ18") (pin "P$2") (pinfunction "2_P$2") (pintype "passive"))
      (node (ref "SJ3") (pin "P$2") (pinfunction "2_P$2") (pintype "passive"))
      (node (ref "U10") (pin "6") (pinfunction "VDD_6") (pintype "power_in"))
      (node (ref "U2") (pin "1") (pinfunction "VIN_1") (pintype "bidirectional"))
      (node (ref "U5") (pin "6") (pinfunction "VDD_6") (pintype "power_in"))
      (node (ref "U6") (pin "4") (pinfunction "V+_4") (pintype "power_in"))
      (node (ref "U7") (pin "6") (pinfunction "VDD_6") (pintype "power_in"))
      (node (ref "U8") (pin "6") (pinfunction "VDD_6") (pintype "power_in"))
      (node (ref "U9") (pin "4") (pinfunction "V+_4") (pintype "power_in"))
    )
    (net (code "4") (name "/AGND") (class "Default")
      (node (ref "G1") (pin "AGND") (pinfunction "AGND_AGND") (pintype "power_in"))
    )
    (net (code "5") (name "/AVDD") (class "Default")
      (node (ref "G1") (pin "AVDD") (pinfunction "AVDD_AVDD") (pintype "power_in"))
    )
    (net (code "6") (name "/CANH") (class "Default")
      (node (ref "IC2") (pin "7") (pinfunction "CANH_7") (pintype "bidirectional"))
      (node (ref "U1") (pin "7") (pinfunction "CANH_7") (pintype "bidirectional"))
      (node (ref "X1") (pin "1") (pinfunction "1_1") (pintype "passive"))
      (node (ref "X2") (pin "1") (pinfunction "1_1") (pintype "passive"))
    )
    (net (code "7") (name "/CANL") (class "Default")
      (node (ref "IC2") (pin "6") (pinfunction "CANL_6") (pintype "bidirectional"))
      (node (ref "U1") (pin "6") (pinfunction "CANL_6") (pintype "bidirectional"))
      (node (ref "X1") (pin "2") (pinfunction "2_2") (pintype "passive"))
      (node (ref "X2") (pin "2") (pinfunction "2_2") (pintype "passive"))
    )
    (net (code "8") (name "/GND4") (class "Default")
      (node (ref "G1") (pin "GND4") (pinfunction "GND4_GND4") (pintype "power_in"))
    )
    (net (code "9") (name "/PWR_POS") (class "Default")
      (node (ref "R17") (pin "2") (pinfunction "2_2") (pintype "passive"))
      (node (ref "X1") (pin "8") (pinfunction "8_8") (pintype "passive"))
      (node (ref "X2") (pin "8") (pinfunction "8_8") (pintype "passive"))
    )
    (net (code "10") (name "/U5V") (class "Default")
      (node (ref "G1") (pin "U5V") (pinfunction "U5V_U5V") (pintype "power_in"))
    )
    (net (code "11") (name "/VBAT") (class "Default")
      (node (ref "G1") (pin "VBAT") (pinfunction "VBAT_VBAT") (pintype "power_in"))
    )
    (net (code "12") (name "/VDD") (class "Default")
      (node (ref "G1") (pin "VDD") (pinfunction "VDD_VDD") (pintype "power_in"))
    )
    (net (code "13") (name "CANRX") (class "Default")
      (node (ref "G1") (pin "PB8") (pinfunction "PB8_PB8") (pintype "bidirectional"))
      (node (ref "IC2") (pin "4") (pinfunction "RXD_4") (pintype "bidirectional"))
      (node (ref "U1") (pin "4") (pinfunction "RXD_4") (pintype "output"))
    )
    (net (code "14") (name "CANTX") (class "Default")
      (node (ref "G1") (pin "PB9") (pinfunction "PB9_PB9") (pintype "bidirectional"))
      (node (ref "IC2") (pin "1") (pinfunction "TXD_1") (pintype "bidirectional"))
      (node (ref "U1") (pin "1") (pinfunction "TXD_1") (pintype "input"))
    )
    (net (code "15") (name "E_CS") (class "Default")
      (node (ref "G1") (pin "PC10") (pinfunction "PC10_PC10") (pintype "bidirectional"))
      (node (ref "JP5") (pin "4") (pinfunction "4_4") (pintype "passive"))
      (node (ref "R1") (pin "2") (pinfunction "2_2") (pintype "passive"))
    )
    (net (code "16") (name "E_LAT") (class "Default")
      (node (ref "G1") (pin "PC11") (pinfunction "PC11_PC11") (pintype "bidirectional"))
      (node (ref "JP5") (pin "5") (pinfunction "5_5") (pintype "passive"))
      (node (ref "R2") (pin "2") (pinfunction "2_2") (pintype "passive"))
    )
    (net (code "17") (name "GND") (class "Default")
      (node (ref "C1") (pin "2") (pinfunction "2_2") (pintype "passive"))
      (node (ref "C10") (pin "2") (pinfunction "2_2") (pintype "passive"))
      (node (ref "C11") (pin "2") (pinfunction "2_2") (pintype "passive"))
      (node (ref "C2") (pin "2") (pinfunction "2_2") (pintype "passive"))
      (node (ref "C3") (pin "2") (pinfunction "2_2") (pintype "passive"))
      (node (ref "C4") (pin "2") (pinfunction "2_2") (pintype "passive"))
      (node (ref "C5") (pin "2") (pinfunction "2_2") (pintype "passive"))
      (node (ref "C6") (pin "-") (pinfunction "-_-") (pintype "passive"))
      (node (ref "C7") (pin "2") (pinfunction "2_2") (pintype "passive"))
      (node (ref "C8") (pin "2") (pinfunction "2_2") (pintype "passive"))
      (node (ref "C9") (pin "2") (pinfunction "2_2") (pintype "passive"))
      (node (ref "D5") (pin "A") (pinfunction "A_A") (pintype "passive"))
      (node (ref "D6") (pin "A") (pinfunction "A_A") (pintype "passive"))
      (node (ref "G1") (pin "GND3") (pinfunction "GND3_GND3") (pintype "power_in"))
      (node (ref "G1") (pin "GND5") (pinfunction "GND5_GND5") (pintype "power_in"))
      (node (ref "G1") (pin "GND6") (pinfunction "GND6_GND6") (pintype "power_in"))
      (node (ref "G1") (pin "GND7") (pinfunction "GND7_GND7") (pintype "power_in"))
      (node (ref "G1") (pin "GND8") (pinfunction "GND8_GND8") (pintype "power_in"))
      (node (ref "IC1") (pin "2") (pinfunction "GNDSIG_2") (pintype "input"))
      (node (ref "IC1") (pin "3") (pinfunction "~{ON/OFF}_3") (pintype "input"))
      (node (ref "IC1") (pin "4") (pinfunction "GND_4") (pintype "power_in"))
      (node (ref "IC2") (pin "2") (pinfunction "VSS_2") (pintype "power_in"))
      (node (ref "J1") (pin "2") (pinfunction "2_2") (pintype "passive"))
      (node (ref "J1") (pin "3") (pinfunction "3_3") (pintype "passive"))
      (node (ref "JP1") (pin "5") (pinfunction "5_5") (pintype "passive"))
      (node (ref "JP1") (pin "6") (pinfunction "6_6") (pintype "passive"))
      (node (ref "JP10") (pin "5") (pinfunction "5_5") (pintype "passive"))
      (node (ref "JP2") (pin "5") (pinfunction "5_5") (pintype "passive"))
      (node (ref "JP2") (pin "6") (pinfunction "6_6") (pintype "passive"))
      (node (ref "JP3") (pin "5") (pinfunction "5_5") (pintype "passive"))
      (node (ref "JP3") (pin "6") (pinfunction "6_6") (pintype "passive"))
      (node (ref "JP4") (pin "5") (pinfunction "5_5") (pintype "passive"))
      (node (ref "JP4") (pin "6") (pinfunction "6_6") (pintype "passive"))
      (node (ref "JP5") (pin "8") (pinfunction "8_8") (pintype "passive"))
      (node (ref "JP6") (pin "4") (pinfunction "4_4") (pintype "passive"))
      (node (ref "JP8") (pin "5") (pinfunction "5_5") (pintype "passive"))
      (node (ref "JP9") (pin "5") (pinfunction "5_5") (pintype "passive"))
      (node (ref "Q1") (pin "2") (pinfunction "S_2") (pintype "passive"))
      (node (ref "Q10") (pin "2") (pinfunction "S_2") (pintype "passive"))
      (node (ref "Q11") (pin "2") (pinfunction "S_2") (pintype "passive"))
      (node (ref "Q12") (pin "2") (pinfunction "S_2") (pintype "passive"))
      (node (ref "Q13") (pin "2") (pinfunction "S_2") (pintype "passive"))
      (node (ref "Q14") (pin "2") (pinfunction "S_2") (pintype "passive"))
      (node (ref "Q15") (pin "2") (pinfunction "S_2") (pintype "passive"))
      (node (ref "Q16") (pin "2") (pinfunction "S_2") (pintype "passive"))
      (node (ref "Q2") (pin "2") (pinfunction "S_2") (pintype "passive"))
      (node (ref "Q3") (pin "2") (pinfunction "S_2") (pintype "passive"))
      (node (ref "Q4") (pin "2") (pinfunction "S_2") (pintype "passive"))
      (node (ref "Q5") (pin "2") (pinfunction "S_2") (pintype "passive"))
      (node (ref "Q6") (pin "2") (pinfunction "S_2") (pintype "passive"))
      (node (ref "Q7") (pin "2") (pinfunction "S_2") (pintype "passive"))
      (node (ref "Q8") (pin "2") (pinfunction "S_2") (pintype "passive"))
      (node (ref "Q9") (pin "2") (pinfunction "S_2") (pintype "passive"))
      (node (ref "R16") (pin "2") (pinfunction "2_2") (pintype "passive"))
      (node (ref "R51") (pin "1") (pinfunction "1_1") (pintype "passive"))
      (node (ref "SJ12") (pin "2") (pinfunction "2_2") (pintype "passive"))
      (node (ref "SJ13") (pin "P$2") (pinfunction "2_P$2") (pintype "passive"))
      (node (ref "SJ19") (pin "2") (pinfunction "2_2") (pintype "passive"))
      (node (ref "SJ20") (pin "P$2") (pinfunction "2_P$2") (pintype "passive"))
      (node (ref "U1") (pin "2") (pinfunction "GND_2") (pintype "power_in"))
      (node (ref "U10") (pin "3") (pinfunction "VSS_3") (pintype "power_in"))
      (node (ref "U11") (pin "13") (pinfunction "G_13") (pintype "input"))
      (node (ref "U11") (pin "8") (pinfunction "GND_8") (pintype "power_in"))
      (node (ref "U13") (pin "13") (pinfunction "G_13") (pintype "input"))
      (node (ref "U13") (pin "8") (pinfunction "GND_8") (pintype "power_in"))
      (node (ref "U2") (pin "4") (pinfunction "SD_4") (pintype "bidirectional"))
      (node (ref "U2") (pin "5") (pinfunction "GND1_5") (pintype "power_in"))
      (node (ref "U2") (pin "6") (pinfunction "GND2_6") (pintype "power_in"))
      (node (ref "U2") (pin "7") (pinfunction "GND3_7") (pintype "power_in"))
      (node (ref "U2") (pin "8") (pinfunction "GND4_8") (pintype "power_in"))
      (node (ref "U3") (pin "6") (pinfunction "INH_6") (pintype "input"))
      (node (ref "U3") (pin "8") (pinfunction "GND_8") (pintype "power_in"))
      (node (ref "U4") (pin "6") (pinfunction "INH_6") (pintype "input"))
      (node (ref "U4") (pin "8") (pinfunction "GND_8") (pintype "power_in"))
      (node (ref "U5") (pin "3") (pinfunction "VSS_3") (pintype "power_in"))
      (node (ref "U6") (pin "11") (pinfunction "V-_11") (pintype "power_in"))
      (node (ref "U7") (pin "3") (pinfunction "VSS_3") (pintype "power_in"))
      (node (ref "U8") (pin "3") (pinfunction "VSS_3") (pintype "power_in"))
      (node (ref "U9") (pin "11") (pinfunction "V-_11") (pintype "power_in"))
      (node (ref "X1") (pin "3") (pinfunction "3_3") (pintype "passive"))
      (node (ref "X1") (pin "6") (pinfunction "6_6") (pintype "passive"))
      (node (ref "X1") (pin "7") (pinfunction "7_7") (pintype "passive"))
      (node (ref "X2") (pin "3") (pinfunction "3_3") (pintype "passive"))
      (node (ref "X2") (pin "6") (pinfunction "6_6") (pintype "passive"))
      (node (ref "X2") (pin "7") (pinfunction "7_7") (pintype "passive"))
      (node (ref "X3") (pin "2") (pinfunction "2_2") (pintype "passive"))
      (node (ref "X6") (pin "2") (pinfunction "2_2") (pintype "passive"))
    )
    (net (code "18") (name "I2CSCL") (class "Default")
      (node (ref "G1") (pin "PB6") (pinfunction "PB6_PB6") (pintype "bidirectional"))
      (node (ref "JP6") (pin "1") (pinfunction "1_1") (pintype "passive"))
      (node (ref "R15") (pin "2") (pinfunction "2_2") (pintype "passive"))
    )
    (net (code "19") (name "I2CSDA") (class "Default")
      (node (ref "G1") (pin "PB7") (pinfunction "PB7_PB7") (pintype "bidirectional"))
      (node (ref "JP6") (pin "2") (pinfunction "2_2") (pintype "passive"))
      (node (ref "R14") (pin "2") (pinfunction "2_2") (pintype "passive"))
    )
    (net (code "20") (name "ILAT") (class "Default")
      (node (ref "G1") (pin "PA6") (pinfunction "PA6_PA6") (pintype "bidirectional"))
      (node (ref "U3") (pin "15") (pinfunction "SH/~{LD}_15") (pintype "input"))
      (node (ref "U4") (pin "15") (pinfunction "SH/~{LD}_15") (pintype "input"))
    )
    (net (code "21") (name "MISO") (class "Default")
      (node (ref "G1") (pin "PB4") (pinfunction "PB4_PB4") (pintype "bidirectional"))
      (node (ref "JP5") (pin "1") (pinfunction "1_1") (pintype "passive"))
    )
    (net (code "22") (name "MISO2") (class "Default")
      (node (ref "G1") (pin "PC2") (pinfunction "PC2_PC2") (pintype "bidirectional"))
      (node (ref "SJ1") (pin "P$2") (pinfunction "2_P$2") (pintype "passive"))
      (node (ref "SJ7") (pin "P$2") (pinfunction "2_P$2") (pintype "passive"))
      (node (ref "U3") (pin "13") (pinfunction "QH_13") (pintype "output"))
    )
    (net (code "23") (name "MOSI") (class "Default")
      (node (ref "G1") (pin "PB5") (pinfunction "PB5_PB5") (pintype "bidirectional"))
      (node (ref "R4") (pin "1") (pinfunction "1_1") (pintype "passive"))
      (node (ref "SJ14") (pin "P$2") (pinfunction "2_P$2") (pintype "passive"))
      (node (ref "SJ4") (pin "1") (pinfunction "1_1") (pintype "passive"))
      (node (ref "U13") (pin "14") (pinfunction "SER_14") (pintype "input"))
    )
    (net (code "24") (name "Net-(D1-PadA)") (class "Default")
      (node (ref "D1") (pin "A") (pinfunction "A_A") (pintype "passive"))
      (node (ref "D2") (pin "A") (pinfunction "A_A") (pintype "passive"))
      (node (ref "JP7") (pin "4") (pinfunction "4_4") (pintype "passive"))
    )
    (net (code "25") (name "Net-(D1-PadC)") (class "Default")
      (node (ref "D1") (pin "C") (pinfunction "C_C") (pintype "passive"))
      (node (ref "D2") (pin "C") (pinfunction "C_C") (pintype "passive"))
      (node (ref "JP7") (pin "1") (pinfunction "1_1") (pintype "passive"))
    )
    (net (code "26") (name "Net-(D3-PadA)") (class "Default")
      (node (ref "D3") (pin "A") (pinfunction "A_A") (pintype "passive"))
      (node (ref "D4") (pin "A") (pinfunction "A_A") (pintype "passive"))
      (node (ref "J1") (pin "1") (pinfunction "1_1") (pintype "passive"))
      (node (ref "X3") (pin "1") (pinfunction "1_1") (pintype "passive"))
    )
    (net (code "27") (name "Net-(IC1-OUT)") (class "Default")
      (node (ref "D5") (pin "C") (pinfunction "C_C") (pintype "passive"))
      (node (ref "D6") (pin "C") (pinfunction "C_C") (pintype "passive"))
      (node (ref "IC1") (pin "7") (pinfunction "OUT_7") (pintype "passive"))
      (node (ref "L1") (pin "2") (pinfunction "2_2") (pintype "passive"))
      (node (ref "U2") (pin "2") (pinfunction "VOUT_2") (pintype "bidirectional"))
    )
    (net (code "28") (name "Net-(IC2-RS)") (class "Default")
      (node (ref "IC2") (pin "8") (pinfunction "RS_8") (pintype "bidirectional"))
      (node (ref "R16") (pin "1") (pinfunction "1_1") (pintype "passive"))
      (node (ref "U1") (pin "8") (pinfunction "RS_8") (pintype "input"))
    )
    (net (code "29") (name "Net-(IC2-VREF)") (class "Default")
      (node (ref "IC2") (pin "5") (pinfunction "VREF_5") (pintype "bidirectional"))
      (node (ref "SJ6") (pin "P$2") (pinfunction "2_P$2") (pintype "passive"))
      (node (ref "U1") (pin "5") (pinfunction "VREF_5") (pintype "output"))
    )
    (net (code "30") (name "Net-(JP7-Pad3)") (class "Default")
      (node (ref "JP7") (pin "3") (pinfunction "3_3") (pintype "passive"))
      (node (ref "R17") (pin "1") (pinfunction "1_1") (pintype "passive"))
    )
    (net (code "31") (name "Net-(JP8-Pad10)") (class "Default")
      (node (ref "JP8") (pin "10") (pinfunction "10_10") (pintype "passive"))
      (node (ref "R25") (pin "2") (pinfunction "2_2") (pintype "passive"))
      (node (ref "R26") (pin "2") (pinfunction "2_2") (pintype "passive"))
      (node (ref "RN1") (pin "9") (pinfunction "9_9") (pintype "passive"))
      (node (ref "RN2") (pin "1") (pinfunction "1_1") (pintype "passive"))
      (node (ref "X4") (pin "1") (pinfunction "1_1") (pintype "passive"))
    )
    (net (code "32") (name "Net-(JP9-Pad10)") (class "Default")
      (node (ref "JP9") (pin "10") (pinfunction "10_10") (pintype "passive"))
      (node (ref "R41") (pin "2") (pinfunction "2_2") (pintype "passive"))
      (node (ref "R42") (pin "2") (pinfunction "2_2") (pintype "passive"))
      (node (ref "RN3") (pin "9") (pinfunction "9_9") (pintype "passive"))
      (node (ref "RN4") (pin "1") (pinfunction "1_1") (pintype "passive"))
      (node (ref "X5") (pin "1") (pinfunction "1_1") (pintype "passive"))
    )
    (net (code "33") (name "Net-(Q1-D)") (class "Default")
      (node (ref "Q1") (pin "3") (pinfunction "D_3") (pintype "passive"))
      (node (ref "U12") (pin "11") (pinfunction "O8_11") (pintype "open_collector"))
      (node (ref "X8") (pin "8") (pinfunction "8_8") (pintype "passive"))
    )
    (net (code "34") (name "Net-(Q1-G)") (class "Default")
      (node (ref "Q1") (pin "1") (pinfunction "G_1") (pintype "passive"))
      (node (ref "R52") (pin "2") (pinfunction "2_2") (pintype "passive"))
    )
    (net (code "35") (name "Net-(Q2-D)") (class "Default")
      (node (ref "Q2") (pin "3") (pinfunction "D_3") (pintype "passive"))
      (node (ref "U12") (pin "12") (pinfunction "O7_12") (pintype "open_collector"))
      (node (ref "X8") (pin "7") (pinfunction "7_7") (pintype "passive"))
    )
    (net (code "36") (name "Net-(Q2-G)") (class "Default")
      (node (ref "Q2") (pin "1") (pinfunction "G_1") (pintype "passive"))
      (node (ref "R53") (pin "2") (pinfunction "2_2") (pintype "passive"))
    )
    (net (code "37") (name "Net-(Q3-D)") (class "Default")
      (node (ref "Q3") (pin "3") (pinfunction "D_3") (pintype "passive"))
      (node (ref "U12") (pin "13") (pinfunction "O6_13") (pintype "open_collector"))
      (node (ref "X8") (pin "6") (pinfunction "6_6") (pintype "passive"))
    )
    (net (code "38") (name "Net-(Q3-G)") (class "Default")
      (node (ref "Q3") (pin "1") (pinfunction "G_1") (pintype "passive"))
      (node (ref "R54") (pin "2") (pinfunction "2_2") (pintype "passive"))
    )
    (net (code "39") (name "Net-(Q4-D)") (class "Default")
      (node (ref "Q4") (pin "3") (pinfunction "D_3") (pintype "passive"))
      (node (ref "U12") (pin "14") (pinfunction "O5_14") (pintype "open_collector"))
      (node (ref "X8") (pin "5") (pinfunction "5_5") (pintype "passive"))
    )
    (net (code "40") (name "Net-(Q4-G)") (class "Default")
      (node (ref "Q4") (pin "1") (pinfunction "G_1") (pintype "passive"))
      (node (ref "R55") (pin "2") (pinfunction "2_2") (pintype "passive"))
    )
    (net (code "41") (name "Net-(Q5-D)") (class "Default")
      (node (ref "Q5") (pin "3") (pinfunction "D_3") (pintype "passive"))
      (node (ref "U12") (pin "15") (pinfunction "O4_15") (pintype "open_collector"))
      (node (ref "X8") (pin "4") (pinfunction "4_4") (pintype "passive"))
    )
    (net (code "42") (name "Net-(Q5-G)") (class "Default")
      (node (ref "Q5") (pin "1") (pinfunction "G_1") (pintype "passive"))
      (node (ref "R56") (pin "2") (pinfunction "2_2") (pintype "passive"))
    )
    (net (code "43") (name "Net-(Q6-D)") (class "Default")
      (node (ref "Q6") (pin "3") (pinfunction "D_3") (pintype "passive"))
      (node (ref "U12") (pin "16") (pinfunction "O3_16") (pintype "open_collector"))
      (node (ref "X8") (pin "3") (pinfunction "3_3") (pintype "passive"))
    )
    (net (code "44") (name "Net-(Q6-G)") (class "Default")
      (node (ref "Q6") (pin "1") (pinfunction "G_1") (pintype "passive"))
      (node (ref "R57") (pin "2") (pinfunction "2_2") (pintype "passive"))
    )
    (net (code "45") (name "Net-(Q7-D)") (class "Default")
      (node (ref "Q7") (pin "3") (pinfunction "D_3") (pintype "passive"))
      (node (ref "U12") (pin "17") (pinfunction "O2_17") (pintype "open_collector"))
      (node (ref "X8") (pin "2") (pinfunction "2_2") (pintype "passive"))
    )
    (net (code "46") (name "Net-(Q7-G)") (class "Default")
      (node (ref "Q7") (pin "1") (pinfunction "G_1") (pintype "passive"))
      (node (ref "R58") (pin "2") (pinfunction "2_2") (pintype "passive"))
    )
    (net (code "47") (name "Net-(Q8-D)") (class "Default")
      (node (ref "Q8") (pin "3") (pinfunction "D_3") (pintype "passive"))
      (node (ref "U12") (pin "18") (pinfunction "O1_18") (pintype "open_collector"))
      (node (ref "X8") (pin "1") (pinfunction "1_1") (pintype "passive"))
    )
    (net (code "48") (name "Net-(Q8-G)") (class "Default")
      (node (ref "Q8") (pin "1") (pinfunction "G_1") (pintype "passive"))
      (node (ref "R59") (pin "2") (pinfunction "2_2") (pintype "passive"))
    )
    (net (code "49") (name "Net-(Q9-D)") (class "Default")
      (node (ref "Q9") (pin "3") (pinfunction "D_3") (pintype "passive"))
      (node (ref "U14") (pin "11") (pinfunction "O8_11") (pintype "open_collector"))
      (node (ref "X9") (pin "8") (pinfunction "8_8") (pintype "passive"))
    )
    (net (code "50") (name "Net-(Q9-G)") (class "Default")
      (node (ref "Q9") (pin "1") (pinfunction "G_1") (pintype "passive"))
      (node (ref "R60") (pin "2") (pinfunction "2_2") (pintype "passive"))
    )
    (net (code "51") (name "Net-(Q10-D)") (class "Default")
      (node (ref "Q10") (pin "3") (pinfunction "D_3") (pintype "passive"))
      (node (ref "U14") (pin "12") (pinfunction "O7_12") (pintype "open_collector"))
      (node (ref "X9") (pin "7") (pinfunction "7_7") (pintype "passive"))
    )
    (net (code "52") (name "Net-(Q10-G)") (class "Default")
      (node (ref "Q10") (pin "1") (pinfunction "G_1") (pintype "passive"))
      (node (ref "R61") (pin "2") (pinfunction "2_2") (pintype "passive"))
    )
    (net (code "53") (name "Net-(Q11-D)") (class "Default")
      (node (ref "Q11") (pin "3") (pinfunction "D_3") (pintype "passive"))
      (node (ref "U14") (pin "13") (pinfunction "O6_13") (pintype "open_collector"))
      (node (ref "X9") (pin "6") (pinfunction "6_6") (pintype "passive"))
    )
    (net (code "54") (name "Net-(Q11-G)") (class "Default")
      (node (ref "Q11") (pin "1") (pinfunction "G_1") (pintype "passive"))
      (node (ref "R62") (pin "2") (pinfunction "2_2") (pintype "passive"))
    )
    (net (code "55") (name "Net-(Q12-D)") (class "Default")
      (node (ref "Q12") (pin "3") (pinfunction "D_3") (pintype "passive"))
      (node (ref "U14") (pin "14") (pinfunction "O5_14") (pintype "open_collector"))
      (node (ref "X9") (pin "5") (pinfunction "5_5") (pintype "passive"))
    )
    (net (code "56") (name "Net-(Q12-G)") (class "Default")
      (node (ref "Q12") (pin "1") (pinfunction "G_1") (pintype "passive"))
      (node (ref "R63") (pin "2") (pinfunction "2_2") (pintype "passive"))
    )
    (net (code "57") (name "Net-(Q13-D)") (class "Default")
      (node (ref "Q13") (pin "3") (pinfunction "D_3") (pintype "passive"))
      (node (ref "U14") (pin "15") (pinfunction "O4_15") (pintype "open_collector"))
      (node (ref "X9") (pin "4") (pinfunction "4_4") (pintype "passive"))
    )
    (net (code "58") (name "Net-(Q13-G)") (class "Default")
      (node (ref "Q13") (pin "1") (pinfunction "G_1") (pintype "passive"))
      (node (ref "R64") (pin "2") (pinfunction "2_2") (pintype "passive"))
    )
    (net (code "59") (name "Net-(Q14-D)") (class "Default")
      (node (ref "Q14") (pin "3") (pinfunction "D_3") (pintype "passive"))
      (node (ref "U14") (pin "16") (pinfunction "O3_16") (pintype "open_collector"))
      (node (ref "X9") (pin "3") (pinfunction "3_3") (pintype "passive"))
    )
    (net (code "60") (name "Net-(Q14-G)") (class "Default")
      (node (ref "Q14") (pin "1") (pinfunction "G_1") (pintype "passive"))
      (node (ref "R65") (pin "2") (pinfunction "2_2") (pintype "passive"))
    )
    (net (code "61") (name "Net-(Q15-D)") (class "Default")
      (node (ref "Q15") (pin "3") (pinfunction "D_3") (pintype "passive"))
      (node (ref "U14") (pin "17") (pinfunction "O2_17") (pintype "open_collector"))
      (node (ref "X9") (pin "2") (pinfunction "2_2") (pintype "passive"))
    )
    (net (code "62") (name "Net-(Q15-G)") (class "Default")
      (node (ref "Q15") (pin "1") (pinfunction "G_1") (pintype "passive"))
      (node (ref "R66") (pin "2") (pinfunction "2_2") (pintype "passive"))
    )
    (net (code "63") (name "Net-(Q16-D)") (class "Default")
      (node (ref "Q16") (pin "3") (pinfunction "D_3") (pintype "passive"))
      (node (ref "U14") (pin "18") (pinfunction "O1_18") (pintype "open_collector"))
      (node (ref "X9") (pin "1") (pinfunction "1_1") (pintype "passive"))
    )
    (net (code "64") (name "Net-(Q16-G)") (class "Default")
      (node (ref "Q16") (pin "1") (pinfunction "G_1") (pintype "passive"))
      (node (ref "R67") (pin "2") (pinfunction "2_2") (pintype "passive"))
    )
    (net (code "65") (name "Net-(RN2A-2)") (class "Default")
      (node (ref "R25") (pin "1") (pinfunction "1_1") (pintype "passive"))
      (node (ref "RN2") (pin "16") (pinfunction "2_16") (pintype "passive"))
      (node (ref "U3") (pin "14") (pinfunction "H_14") (pintype "input"))
    )
    (net (code "66") (name "Net-(RN2B-1)") (class "Default")
      (node (ref "JP8") (pin "9") (pinfunction "9_9") (pintype "passive"))
      (node (ref "R24") (pin "2") (pinfunction "2_2") (pintype "passive"))
      (node (ref "R27") (pin "2") (pinfunction "2_2") (pintype "passive"))
      (node (ref "RN1") (pin "8") (pinfunction "8_8") (pintype "passive"))
      (node (ref "RN2") (pin "2") (pinfunction "1_2") (pintype "passive"))
      (node (ref "X4") (pin "2") (pinfunction "2_2") (pintype "passive"))
    )
    (net (code "67") (name "Net-(RN2B-2)") (class "Default")
      (node (ref "R24") (pin "1") (pinfunction "1_1") (pintype "passive"))
      (node (ref "RN2") (pin "15") (pinfunction "2_15") (pintype "passive"))
      (node (ref "U3") (pin "12") (pinfunction "G_12") (pintype "input"))
    )
    (net (code "68") (name "Net-(RN2C-1)") (class "Default")
      (node (ref "JP8") (pin "8") (pinfunction "8_8") (pintype "passive"))
      (node (ref "R23") (pin "2") (pinfunction "2_2") (pintype "passive"))
      (node (ref "R28") (pin "2") (pinfunction "2_2") (pintype "passive"))
      (node (ref "RN1") (pin "7") (pinfunction "7_7") (pintype "passive"))
      (node (ref "RN2") (pin "3") (pinfunction "1_3") (pintype "passive"))
      (node (ref "X4") (pin "3") (pinfunction "3_3") (pintype "passive"))
    )
    (net (code "69") (name "Net-(RN2C-2)") (class "Default")
      (node (ref "R23") (pin "1") (pinfunction "1_1") (pintype "passive"))
      (node (ref "RN2") (pin "14") (pinfunction "2_14") (pintype "passive"))
      (node (ref "U3") (pin "11") (pinfunction "F_11") (pintype "input"))
    )
    (net (code "70") (name "Net-(RN2D-1)") (class "Default")
      (node (ref "JP8") (pin "7") (pinfunction "7_7") (pintype "passive"))
      (node (ref "R22") (pin "2") (pinfunction "2_2") (pintype "passive"))
      (node (ref "R29") (pin "2") (pinfunction "2_2") (pintype "passive"))
      (node (ref "RN1") (pin "6") (pinfunction "6_6") (pintype "passive"))
      (node (ref "RN2") (pin "4") (pinfunction "1_4") (pintype "passive"))
      (node (ref "X4") (pin "4") (pinfunction "4_4") (pintype "passive"))
    )
    (net (code "71") (name "Net-(RN2D-2)") (class "Default")
      (node (ref "R22") (pin "1") (pinfunction "1_1") (pintype "passive"))
      (node (ref "RN2") (pin "13") (pinfunction "2_13") (pintype "passive"))
      (node (ref "U3") (pin "10") (pinfunction "E_10") (pintype "input"))
    )
    (net (code "72") (name "Net-(RN2E-1)") (class "Default")
      (node (ref "JP8") (pin "4") (pinfunction "4_4") (pintype "passive"))
      (node (ref "R21") (pin "2") (pinfunction "2_2") (pintype "passive"))
      (node (ref "R30") (pin "2") (pinfunction "2_2") (pintype "passive"))
      (node (ref "RN1") (pin "5") (pinfunction "5_5") (pintype "passive"))
      (node (ref "RN2") (pin "5") (pinfunction "1_5") (pintype "passive"))
      (node (ref "X4") (pin "5") (pinfunction "5_5") (pintype "passive"))
    )
    (net (code "73") (name "Net-(RN2E-2)") (class "Default")
      (node (ref "R21") (pin "1") (pinfunction "1_1") (pintype "passive"))
      (node (ref "RN2") (pin "12") (pinfunction "2_12") (pintype "passive"))
      (node (ref "U3") (pin "5") (pinfunction "D_5") (pintype "input"))
    )
    (net (code "74") (name "Net-(RN2F-1)") (class "Default")
      (node (ref "JP8") (pin "3") (pinfunction "3_3") (pintype "passive"))
      (node (ref "R20") (pin "2") (pinfunction "2_2") (pintype "passive"))
      (node (ref "R31") (pin "2") (pinfunction "2_2") (pintype "passive"))
      (node (ref "RN1") (pin "4") (pinfunction "4_4") (pintype "passive"))
      (node (ref "RN2") (pin "6") (pinfunction "1_6") (pintype "passive"))
      (node (ref "X4") (pin "6") (pinfunction "6_6") (pintype "passive"))
    )
    (net (code "75") (name "Net-(RN2F-2)") (class "Default")
      (node (ref "R20") (pin "1") (pinfunction "1_1") (pintype "passive"))
      (node (ref "RN2") (pin "11") (pinfunction "2_11") (pintype "passive"))
      (node (ref "U3") (pin "4") (pinfunction "C_4") (pintype "input"))
    )
    (net (code "76") (name "Net-(RN2G-1)") (class "Default")
      (node (ref "JP8") (pin "2") (pinfunction "2_2") (pintype "passive"))
      (node (ref "R19") (pin "2") (pinfunction "2_2") (pintype "passive"))
      (node (ref "R32") (pin "2") (pinfunction "2_2") (pintype "passive"))
      (node (ref "RN1") (pin "3") (pinfunction "3_3") (pintype "passive"))
      (node (ref "RN2") (pin "7") (pinfunction "1_7") (pintype "passive"))
      (node (ref "X4") (pin "7") (pinfunction "7_7") (pintype "passive"))
    )
    (net (code "77") (name "Net-(RN2G-2)") (class "Default")
      (node (ref "R19") (pin "1") (pinfunction "1_1") (pintype "passive"))
      (node (ref "RN2") (pin "10") (pinfunction "2_10") (pintype "passive"))
      (node (ref "U3") (pin "3") (pinfunction "B_3") (pintype "input"))
    )
    (net (code "78") (name "Net-(RN2H-1)") (class "Default")
      (node (ref "JP8") (pin "1") (pinfunction "1_1") (pintype "passive"))
      (node (ref "R18") (pin "2") (pinfunction "2_2") (pintype "passive"))
      (node (ref "R33") (pin "2") (pinfunction "2_2") (pintype "passive"))
      (node (ref "RN1") (pin "2") (pinfunction "2_2") (pintype "passive"))
      (node (ref "RN2") (pin "8") (pinfunction "1_8") (pintype "passive"))
      (node (ref "X4") (pin "8") (pinfunction "8_8") (pintype "passive"))
    )
    (net (code "79") (name "Net-(RN2H-2)") (class "Default")
      (node (ref "R18") (pin "1") (pinfunction "1_1") (pintype "passive"))
      (node (ref "RN2") (pin "9") (pinfunction "2_9") (pintype "passive"))
      (node (ref "U3") (pin "2") (pinfunction "A_2") (pintype "input"))
    )
    (net (code "80") (name "Net-(RN4A-2)") (class "Default")
      (node (ref "R41") (pin "1") (pinfunction "1_1") (pintype "passive"))
      (node (ref "RN4") (pin "16") (pinfunction "2_16") (pintype "passive"))
      (node (ref "U4") (pin "14") (pinfunction "H_14") (pintype "input"))
    )
    (net (code "81") (name "Net-(RN4B-1)") (class "Default")
      (node (ref "JP9") (pin "9") (pinfunction "9_9") (pintype "passive"))
      (node (ref "R40") (pin "2") (pinfunction "2_2") (pintype "passive"))
      (node (ref "R43") (pin "2") (pinfunction "2_2") (pintype "passive"))
      (node (ref "RN3") (pin "8") (pinfunction "8_8") (pintype "passive"))
      (node (ref "RN4") (pin "2") (pinfunction "1_2") (pintype "passive"))
      (node (ref "X5") (pin "2") (pinfunction "2_2") (pintype "passive"))
    )
    (net (code "82") (name "Net-(RN4B-2)") (class "Default")
      (node (ref "R40") (pin "1") (pinfunction "1_1") (pintype "passive"))
      (node (ref "RN4") (pin "15") (pinfunction "2_15") (pintype "passive"))
      (node (ref "U4") (pin "12") (pinfunction "G_12") (pintype "input"))
    )
    (net (code "83") (name "Net-(RN4C-1)") (class "Default")
      (node (ref "JP9") (pin "8") (pinfunction "8_8") (pintype "passive"))
      (node (ref "R39") (pin "2") (pinfunction "2_2") (pintype "passive"))
      (node (ref "R44") (pin "2") (pinfunction "2_2") (pintype "passive"))
      (node (ref "RN3") (pin "7") (pinfunction "7_7") (pintype "passive"))
      (node (ref "RN4") (pin "3") (pinfunction "1_3") (pintype "passive"))
      (node (ref "X5") (pin "3") (pinfunction "3_3") (pintype "passive"))
    )
    (net (code "84") (name "Net-(RN4C-2)") (class "Default")
      (node (ref "R39") (pin "1") (pinfunction "1_1") (pintype "passive"))
      (node (ref "RN4") (pin "14") (pinfunction "2_14") (pintype "passive"))
      (node (ref "U4") (pin "11") (pinfunction "F_11") (pintype "input"))
    )
    (net (code "85") (name "Net-(RN4D-1)") (class "Default")
      (node (ref "JP9") (pin "7") (pinfunction "7_7") (pintype "passive"))
      (node (ref "R38") (pin "2") (pinfunction "2_2") (pintype "passive"))
      (node (ref "R45") (pin "2") (pinfunction "2_2") (pintype "passive"))
      (node (ref "RN3") (pin "6") (pinfunction "6_6") (pintype "passive"))
      (node (ref "RN4") (pin "4") (pinfunction "1_4") (pintype "passive"))
      (node (ref "X5") (pin "4") (pinfunction "4_4") (pintype "passive"))
    )
    (net (code "86") (name "Net-(RN4D-2)") (class "Default")
      (node (ref "R38") (pin "1") (pinfunction "1_1") (pintype "passive"))
      (node (ref "RN4") (pin "13") (pinfunction "2_13") (pintype "passive"))
      (node (ref "U4") (pin "10") (pinfunction "E_10") (pintype "input"))
    )
    (net (code "87") (name "Net-(RN4E-1)") (class "Default")
      (node (ref "JP9") (pin "4") (pinfunction "4_4") (pintype "passive"))
      (node (ref "R37") (pin "2") (pinfunction "2_2") (pintype "passive"))
      (node (ref "R46") (pin "2") (pinfunction "2_2") (pintype "passive"))
      (node (ref "RN3") (pin "5") (pinfunction "5_5") (pintype "passive"))
      (node (ref "RN4") (pin "5") (pinfunction "1_5") (pintype "passive"))
      (node (ref "X5") (pin "5") (pinfunction "5_5") (pintype "passive"))
    )
    (net (code "88") (name "Net-(RN4E-2)") (class "Default")
      (node (ref "R37") (pin "1") (pinfunction "1_1") (pintype "passive"))
      (node (ref "RN4") (pin "12") (pinfunction "2_12") (pintype "passive"))
      (node (ref "U4") (pin "5") (pinfunction "D_5") (pintype "input"))
    )
    (net (code "89") (name "Net-(RN4F-1)") (class "Default")
      (node (ref "JP9") (pin "3") (pinfunction "3_3") (pintype "passive"))
      (node (ref "R36") (pin "2") (pinfunction "2_2") (pintype "passive"))
      (node (ref "R47") (pin "2") (pinfunction "2_2") (pintype "passive"))
      (node (ref "RN3") (pin "4") (pinfunction "4_4") (pintype "passive"))
      (node (ref "RN4") (pin "6") (pinfunction "1_6") (pintype "passive"))
      (node (ref "X5") (pin "6") (pinfunction "6_6") (pintype "passive"))
    )
    (net (code "90") (name "Net-(RN4F-2)") (class "Default")
      (node (ref "R36") (pin "1") (pinfunction "1_1") (pintype "passive"))
      (node (ref "RN4") (pin "11") (pinfunction "2_11") (pintype "passive"))
      (node (ref "U4") (pin "4") (pinfunction "C_4") (pintype "input"))
    )
    (net (code "91") (name "Net-(RN4G-1)") (class "Default")
      (node (ref "JP9") (pin "2") (pinfunction "2_2") (pintype "passive"))
      (node (ref "R35") (pin "2") (pinfunction "2_2") (pintype "passive"))
      (node (ref "R48") (pin "2") (pinfunction "2_2") (pintype "passive"))
      (node (ref "RN3") (pin "3") (pinfunction "3_3") (pintype "passive"))
      (node (ref "RN4") (pin "7") (pinfunction "1_7") (pintype "passive"))
      (node (ref "X5") (pin "7") (pinfunction "7_7") (pintype "passive"))
    )
    (net (code "92") (name "Net-(RN4G-2)") (class "Default")
      (node (ref "R35") (pin "1") (pinfunction "1_1") (pintype "passive"))
      (node (ref "RN4") (pin "10") (pinfunction "2_10") (pintype "passive"))
      (node (ref "U4") (pin "3") (pinfunction "B_3") (pintype "input"))
    )
    (net (code "93") (name "Net-(RN4H-1)") (class "Default")
      (node (ref "JP9") (pin "1") (pinfunction "1_1") (pintype "passive"))
      (node (ref "R34") (pin "2") (pinfunction "2_2") (pintype "passive"))
      (node (ref "R49") (pin "2") (pinfunction "2_2") (pintype "passive"))
      (node (ref "RN3") (pin "2") (pinfunction "2_2") (pintype "passive"))
      (node (ref "RN4") (pin "8") (pinfunction "1_8") (pintype "passive"))
      (node (ref "X5") (pin "8") (pinfunction "8_8") (pintype "passive"))
    )
    (net (code "94") (name "Net-(RN4H-2)") (class "Default")
      (node (ref "R34") (pin "1") (pinfunction "1_1") (pintype "passive"))
      (node (ref "RN4") (pin "9") (pinfunction "2_9") (pintype "passive"))
      (node (ref "U4") (pin "2") (pinfunction "A_2") (pintype "input"))
    )
    (net (code "95") (name "Net-(SJ1-1)") (class "Default")
      (node (ref "G1") (pin "PB14") (pinfunction "PB14_PB14") (pintype "bidirectional"))
      (node (ref "SJ1") (pin "P$1") (pinfunction "1_P$1") (pintype "passive"))
    )
    (net (code "96") (name "Net-(SJ2-2)") (class "Default")
      (node (ref "G1") (pin "PB13") (pinfunction "PB13_PB13") (pintype "bidirectional"))
      (node (ref "SJ2") (pin "P$2") (pinfunction "2_P$2") (pintype "passive"))
    )
    (net (code "97") (name "Net-(SJ3-1)") (class "Default")
      (node (ref "G1") (pin "VIN2") (pinfunction "VIN2_VIN2") (pintype "power_in"))
      (node (ref "SJ3") (pin "P$1") (pinfunction "1_P$1") (pintype "passive"))
    )
    (net (code "98") (name "Net-(SJ5-2)") (class "Default")
      (node (ref "JP5") (pin "2") (pinfunction "2_2") (pintype "passive"))
      (node (ref "SJ4") (pin "2") (pinfunction "2_2") (pintype "passive"))
      (node (ref "SJ5") (pin "P$2") (pinfunction "2_P$2") (pintype "passive"))
    )
    (net (code "99") (name "Net-(SJ10-1)") (class "Default")
      (node (ref "SJ10") (pin "P$1") (pinfunction "1_P$1") (pintype "passive"))
      (node (ref "SJ12") (pin "1") (pinfunction "1_1") (pintype "passive"))
      (node (ref "SJ8") (pin "P$1") (pinfunction "1_P$1") (pintype "passive"))
      (node (ref "U12") (pin "9") (pinfunction "GND_9") (pintype "power_in"))
    )
    (net (code "100") (name "Net-(SJ11-1)") (class "Default")
      (node (ref "SJ11") (pin "P$1") (pinfunction "1_P$1") (pintype "passive"))
      (node (ref "SJ13") (pin "P$1") (pinfunction "1_P$1") (pintype "passive"))
      (node (ref "SJ9") (pin "P$1") (pinfunction "1_P$1") (pintype "passive"))
      (node (ref "U12") (pin "10") (pinfunction "CD+_10") (pintype "passive"))
      (node (ref "X8") (pin "9") (pinfunction "9_9") (pintype "passive"))
    )
    (net (code "101") (name "Net-(SJ15-1)") (class "Default")
      (node (ref "SJ15") (pin "P$1") (pinfunction "1_P$1") (pintype "passive"))
      (node (ref "SJ17") (pin "P$1") (pinfunction "1_P$1") (pintype "passive"))
      (node (ref "SJ19") (pin "1") (pinfunction "1_1") (pintype "passive"))
      (node (ref "U14") (pin "9") (pinfunction "GND_9") (pintype "power_in"))
    )
    (net (code "102") (name "Net-(SJ16-1)") (class "Default")
      (node (ref "SJ16") (pin "P$1") (pinfunction "1_P$1") (pintype "passive"))
      (node (ref "SJ18") (pin "P$1") (pinfunction "1_P$1") (pintype "passive"))
      (node (ref "SJ20") (pin "P$1") (pinfunction "1_P$1") (pintype "passive"))
      (node (ref "U14") (pin "10") (pinfunction "CD+_10") (pintype "passive"))
      (node (ref "X9") (pin "9") (pinfunction "9_9") (pintype "passive"))
    )
    (net (code "103") (name "Net-(U5A-O)") (class "Default")
      (node (ref "JP10") (pin "10") (pinfunction "10_10") (pintype "passive"))
      (node (ref "U5") (pin "7") (pinfunction "O_7") (pintype "output"))
      (node (ref "U6") (pin "7") (pinfunction "OUT_7") (pintype "output"))
      (node (ref "X7") (pin "1") (pinfunction "1_1") (pintype "passive"))
    )
    (net (code "104") (name "Net-(U5B-O)") (class "Default")
      (node (ref "JP10") (pin "9") (pinfunction "9_9") (pintype "passive"))
      (node (ref "U5") (pin "5") (pinfunction "O_5") (pintype "output"))
      (node (ref "U6") (pin "8") (pinfunction "OUT_8") (pintype "output"))
      (node (ref "X7") (pin "2") (pinfunction "2_2") (pintype "passive"))
    )
    (net (code "105") (name "Net-(U6A--IN)") (class "Default")
      (node (ref "R50") (pin "1") (pinfunction "1_1") (pintype "passive"))
      (node (ref "R51") (pin "2") (pinfunction "2_2") (pintype "passive"))
      (node (ref "U6") (pin "13") (pinfunction "-IN_13") (pintype "input"))
      (node (ref "U6") (pin "2") (pinfunction "-IN_2") (pintype "input"))
      (node (ref "U6") (pin "6") (pinfunction "-IN_6") (pintype "input"))
      (node (ref "U6") (pin "9") (pinfunction "-IN_9") (pintype "input"))
      (node (ref "U9") (pin "13") (pinfunction "-IN_13") (pintype "input"))
      (node (ref "U9") (pin "2") (pinfunction "-IN_2") (pintype "input"))
      (node (ref "U9") (pin "6") (pinfunction "-IN_6") (pintype "input"))
      (node (ref "U9") (pin "9") (pinfunction "-IN_9") (pintype "input"))
    )
    (net (code "106") (name "Net-(U6A-OUT)") (class "Default")
      (node (ref "JP10") (pin "8") (pinfunction "8_8") (pintype "passive"))
      (node (ref "U6") (pin "1") (pinfunction "OUT_1") (pintype "output"))
      (node (ref "U7") (pin "5") (pinfunction "O_5") (pintype "output"))
      (node (ref "X7") (pin "3") (pinfunction "3_3") (pintype "passive"))
    )
    (net (code "107") (name "Net-(U6D-OUT)") (class "Default")
      (node (ref "JP10") (pin "7") (pinfunction "7_7") (pintype "passive"))
      (node (ref "U6") (pin "14") (pinfunction "OUT_14") (pintype "output"))
      (node (ref "U7") (pin "7") (pinfunction "O_7") (pintype "output"))
      (node (ref "X7") (pin "4") (pinfunction "4_4") (pintype "passive"))
    )
    (net (code "108") (name "Net-(U8A-O)") (class "Default")
      (node (ref "JP10") (pin "4") (pinfunction "4_4") (pintype "passive"))
      (node (ref "U8") (pin "7") (pinfunction "O_7") (pintype "output"))
      (node (ref "U9") (pin "7") (pinfunction "OUT_7") (pintype "output"))
      (node (ref "X7") (pin "5") (pinfunction "5_5") (pintype "passive"))
    )
    (net (code "109") (name "Net-(U8B-O)") (class "Default")
      (node (ref "JP10") (pin "3") (pinfunction "3_3") (pintype "passive"))
      (node (ref "U8") (pin "5") (pinfunction "O_5") (pintype "output"))
      (node (ref "U9") (pin "8") (pinfunction "OUT_8") (pintype "output"))
      (node (ref "X7") (pin "6") (pinfunction "6_6") (pintype "passive"))
    )
    (net (code "110") (name "Net-(U10A-O)") (class "Default")
      (node (ref "JP10") (pin "1") (pinfunction "1_1") (pintype "passive"))
      (node (ref "U10") (pin "7") (pinfunction "O_7") (pintype "output"))
      (node (ref "U9") (pin "14") (pinfunction "OUT_14") (pintype "output"))
      (node (ref "X7") (pin "8") (pinfunction "8_8") (pintype "passive"))
    )
    (net (code "111") (name "Net-(U10B-O)") (class "Default")
      (node (ref "JP10") (pin "2") (pinfunction "2_2") (pintype "passive"))
      (node (ref "U10") (pin "5") (pinfunction "O_5") (pintype "output"))
      (node (ref "U9") (pin "1") (pinfunction "OUT_1") (pintype "output"))
      (node (ref "X7") (pin "7") (pinfunction "7_7") (pintype "passive"))
    )
    (net (code "112") (name "Net-(U11A-QA)") (class "Default")
      (node (ref "R59") (pin "1") (pinfunction "1_1") (pintype "passive"))
      (node (ref "U11") (pin "15") (pinfunction "QA_15") (pintype "tri_state"))
      (node (ref "U12") (pin "1") (pinfunction "I1_1") (pintype "input"))
    )
    (net (code "113") (name "Net-(U11A-QB)") (class "Default")
      (node (ref "R58") (pin "1") (pinfunction "1_1") (pintype "passive"))
      (node (ref "U11") (pin "1") (pinfunction "QB_1") (pintype "tri_state"))
      (node (ref "U12") (pin "2") (pinfunction "I2_2") (pintype "input"))
    )
    (net (code "114") (name "Net-(U11A-QC)") (class "Default")
      (node (ref "R57") (pin "1") (pinfunction "1_1") (pintype "passive"))
      (node (ref "U11") (pin "2") (pinfunction "QC_2") (pintype "tri_state"))
      (node (ref "U12") (pin "3") (pinfunction "I3_3") (pintype "input"))
    )
    (net (code "115") (name "Net-(U11A-QD)") (class "Default")
      (node (ref "R56") (pin "1") (pinfunction "1_1") (pintype "passive"))
      (node (ref "U11") (pin "3") (pinfunction "QD_3") (pintype "tri_state"))
      (node (ref "U12") (pin "4") (pinfunction "I4_4") (pintype "input"))
    )
    (net (code "116") (name "Net-(U11A-QE)") (class "Default")
      (node (ref "R55") (pin "1") (pinfunction "1_1") (pintype "passive"))
      (node (ref "U11") (pin "4") (pinfunction "QE_4") (pintype "tri_state"))
      (node (ref "U12") (pin "5") (pinfunction "I5_5") (pintype "input"))
    )
    (net (code "117") (name "Net-(U11A-QF)") (class "Default")
      (node (ref "R54") (pin "1") (pinfunction "1_1") (pintype "passive"))
      (node (ref "U11") (pin "5") (pinfunction "QF_5") (pintype "tri_state"))
      (node (ref "U12") (pin "6") (pinfunction "I6_6") (pintype "input"))
    )
    (net (code "118") (name "Net-(U11A-QG)") (class "Default")
      (node (ref "R53") (pin "1") (pinfunction "1_1") (pintype "passive"))
      (node (ref "U11") (pin "6") (pinfunction "QG_6") (pintype "tri_state"))
      (node (ref "U12") (pin "7") (pinfunction "I7_7") (pintype "input"))
    )
    (net (code "119") (name "Net-(U11A-QH)") (class "Default")
      (node (ref "R52") (pin "1") (pinfunction "1_1") (pintype "passive"))
      (node (ref "U11") (pin "7") (pinfunction "QH_7") (pintype "tri_state"))
      (node (ref "U12") (pin "8") (pinfunction "I8_8") (pintype "input"))
    )
    (net (code "120") (name "Net-(U13A-QA)") (class "Default")
      (node (ref "R67") (pin "1") (pinfunction "1_1") (pintype "passive"))
      (node (ref "U13") (pin "15") (pinfunction "QA_15") (pintype "tri_state"))
      (node (ref "U14") (pin "1") (pinfunction "I1_1") (pintype "input"))
    )
    (net (code "121") (name "Net-(U13A-QB)") (class "Default")
      (node (ref "R66") (pin "1") (pinfunction "1_1") (pintype "passive"))
      (node (ref "U13") (pin "1") (pinfunction "QB_1") (pintype "tri_state"))
      (node (ref "U14") (pin "2") (pinfunction "I2_2") (pintype "input"))
    )
    (net (code "122") (name "Net-(U13A-QC)") (class "Default")
      (node (ref "R65") (pin "1") (pinfunction "1_1") (pintype "passive"))
      (node (ref "U13") (pin "2") (pinfunction "QC_2") (pintype "tri_state"))
      (node (ref "U14") (pin "3") (pinfunction "I3_3") (pintype "input"))
    )
    (net (code "123") (name "Net-(U13A-QD)") (class "Default")
      (node (ref "R64") (pin "1") (pinfunction "1_1") (pintype "passive"))
      (node (ref "U13") (pin "3") (pinfunction "QD_3") (pintype "tri_state"))
      (node (ref "U14") (pin "4") (pinfunction "I4_4") (pintype "input"))
    )
    (net (code "124") (name "Net-(U13A-QE)") (class "Default")
      (node (ref "R63") (pin "1") (pinfunction "1_1") (pintype "passive"))
      (node (ref "U13") (pin "4") (pinfunction "QE_4") (pintype "tri_state"))
      (node (ref "U14") (pin "5") (pinfunction "I5_5") (pintype "input"))
    )
    (net (code "125") (name "Net-(U13A-QF)") (class "Default")
      (node (ref "R62") (pin "1") (pinfunction "1_1") (pintype "passive"))
      (node (ref "U13") (pin "5") (pinfunction "QF_5") (pintype "tri_state"))
      (node (ref "U14") (pin "6") (pinfunction "I6_6") (pintype "input"))
    )
    (net (code "126") (name "Net-(U13A-QG)") (class "Default")
      (node (ref "R61") (pin "1") (pinfunction "1_1") (pintype "passive"))
      (node (ref "U13") (pin "6") (pinfunction "QG_6") (pintype "tri_state"))
      (node (ref "U14") (pin "7") (pinfunction "I7_7") (pintype "input"))
    )
    (net (code "127") (name "Net-(U13A-QH)") (class "Default")
      (node (ref "R60") (pin "1") (pinfunction "1_1") (pintype "passive"))
      (node (ref "U13") (pin "7") (pinfunction "QH_7") (pintype "tri_state"))
      (node (ref "U14") (pin "8") (pinfunction "I8_8") (pintype "input"))
    )
    (net (code "128") (name "Net-(X1-Pad4)") (class "Default")
      (node (ref "X1") (pin "4") (pinfunction "4_4") (pintype "passive"))
      (node (ref "X2") (pin "4") (pinfunction "4_4") (pintype "passive"))
    )
    (net (code "129") (name "Net-(X1-Pad5)") (class "Default")
      (node (ref "X1") (pin "5") (pinfunction "5_5") (pintype "passive"))
      (node (ref "X2") (pin "5") (pinfunction "5_5") (pintype "passive"))
    )
    (net (code "130") (name "OLAT") (class "Default")
      (node (ref "G1") (pin "PA8") (pinfunction "PA8_PA8") (pintype "bidirectional"))
      (node (ref "R3") (pin "1") (pinfunction "1_1") (pintype "passive"))
      (node (ref "U11") (pin "12") (pinfunction "RCK_12") (pintype "input"))
      (node (ref "U13") (pin "12") (pinfunction "RCK_12") (pintype "input"))
    )
    (net (code "131") (name "SCK") (class "Default")
      (node (ref "G1") (pin "PB3") (pinfunction "PB3_PB3") (pintype "bidirectional"))
      (node (ref "JP5") (pin "3") (pinfunction "3_3") (pintype "passive"))
      (node (ref "R5") (pin "1") (pinfunction "1_1") (pintype "passive"))
      (node (ref "U11") (pin "11") (pinfunction "SCK_11") (pintype "input"))
      (node (ref "U13") (pin "11") (pinfunction "SCK_11") (pintype "input"))
    )
    (net (code "132") (name "SCK2") (class "Default")
      (node (ref "G1") (pin "PB10") (pinfunction "PB10_PB10") (pintype "bidirectional"))
      (node (ref "SJ2") (pin "P$1") (pinfunction "1_P$1") (pintype "passive"))
      (node (ref "U3") (pin "7") (pinfunction "CLK_7") (pintype "input"))
      (node (ref "U4") (pin "7") (pinfunction "CLK_7") (pintype "input"))
    )
    (net (code "133") (name "SLNK1") (class "Default")
      (node (ref "SJ14") (pin "P$1") (pinfunction "1_P$1") (pintype "passive"))
      (node (ref "U11") (pin "14") (pinfunction "SER_14") (pintype "input"))
      (node (ref "U13") (pin "9") (pinfunction "QH*_9") (pintype "tri_state"))
    )
    (net (code "134") (name "SLNK2") (class "Default")
      (node (ref "SJ5") (pin "P$1") (pinfunction "1_P$1") (pintype "passive"))
      (node (ref "U11") (pin "9") (pinfunction "QH*_9") (pintype "tri_state"))
    )
    (net (code "135") (name "SLNK3") (class "Default")
      (node (ref "SJ7") (pin "P$1") (pinfunction "1_P$1") (pintype "passive"))
      (node (ref "U3") (pin "1") (pinfunction "SER_1") (pintype "input"))
      (node (ref "U4") (pin "13") (pinfunction "QH_13") (pintype "output"))
    )
    (net (code "136") (name "SRV1") (class "Default")
      (node (ref "G1") (pin "PC9") (pinfunction "PC9_PC9") (pintype "bidirectional"))
      (node (ref "JP4") (pin "2") (pinfunction "2_2") (pintype "passive"))
      (node (ref "R13") (pin "2") (pinfunction "2_2") (pintype "passive"))
    )
    (net (code "137") (name "SRV2") (class "Default")
      (node (ref "G1") (pin "PC7") (pinfunction "PC7_PC7") (pintype "bidirectional"))
      (node (ref "JP4") (pin "1") (pinfunction "1_1") (pintype "passive"))
      (node (ref "R12") (pin "2") (pinfunction "2_2") (pintype "passive"))
    )
    (net (code "138") (name "SRV3") (class "Default")
      (node (ref "G1") (pin "PC8") (pinfunction "PC8_PC8") (pintype "bidirectional"))
      (node (ref "JP3") (pin "2") (pinfunction "2_2") (pintype "passive"))
      (node (ref "R11") (pin "2") (pinfunction "2_2") (pintype "passive"))
    )
    (net (code "139") (name "SRV4") (class "Default")
      (node (ref "G1") (pin "PC6") (pinfunction "PC6_PC6") (pintype "bidirectional"))
      (node (ref "JP3") (pin "1") (pinfunction "1_1") (pintype "passive"))
      (node (ref "R10") (pin "2") (pinfunction "2_2") (pintype "passive"))
    )
    (net (code "140") (name "SRV5") (class "Default")
      (node (ref "G1") (pin "PC12") (pinfunction "PC12_PC12") (pintype "bidirectional"))
      (node (ref "JP2") (pin "2") (pinfunction "2_2") (pintype "passive"))
      (node (ref "R9") (pin "2") (pinfunction "2_2") (pintype "passive"))
    )
    (net (code "141") (name "SRV6") (class "Default")
      (node (ref "G1") (pin "PA15") (pinfunction "PA15_PA15") (pintype "bidirectional"))
      (node (ref "JP2") (pin "1") (pinfunction "1_1") (pintype "passive"))
      (node (ref "R8") (pin "2") (pinfunction "2_2") (pintype "passive"))
    )
    (net (code "142") (name "SRV7") (class "Default")
      (node (ref "G1") (pin "PF1-PH1") (pinfunction "PF1-PH1_PF1-PH1") (pintype "bidirectional"))
      (node (ref "JP1") (pin "2") (pinfunction "2_2") (pintype "passive"))
      (node (ref "R7") (pin "2") (pinfunction "2_2") (pintype "passive"))
    )
    (net (code "143") (name "SRV8") (class "Default")
      (node (ref "G1") (pin "PD2") (pinfunction "PD2_PD2") (pintype "bidirectional"))
      (node (ref "JP1") (pin "1") (pinfunction "1_1") (pintype "passive"))
      (node (ref "R6") (pin "2") (pinfunction "2_2") (pintype "passive"))
    )
    (net (code "144") (name "TDRV1") (class "Default")
      (node (ref "G1") (pin "PB12") (pinfunction "PB12_PB12") (pintype "bidirectional"))
      (node (ref "U10") (pin "2") (pinfunction "I_2") (pintype "input"))
      (node (ref "U9") (pin "12") (pinfunction "+IN_12") (pintype "input"))
    )
    (net (code "145") (name "TDRV2") (class "Default")
      (node (ref "G1") (pin "PB2") (pinfunction "PB2_PB2") (pintype "bidirectional"))
      (node (ref "U10") (pin "4") (pinfunction "I_4") (pintype "input"))
      (node (ref "U9") (pin "3") (pinfunction "+IN_3") (pintype "input"))
    )
    (net (code "146") (name "TDRV3") (class "Default")
      (node (ref "G1") (pin "PB15") (pinfunction "PB15_PB15") (pintype "bidirectional"))
      (node (ref "U8") (pin "4") (pinfunction "I_4") (pintype "input"))
      (node (ref "U9") (pin "10") (pinfunction "+IN_10") (pintype "input"))
    )
    (net (code "147") (name "TDRV4") (class "Default")
      (node (ref "G1") (pin "PB1") (pinfunction "PB1_PB1") (pintype "bidirectional"))
      (node (ref "U8") (pin "2") (pinfunction "I_2") (pintype "input"))
      (node (ref "U9") (pin "5") (pinfunction "+IN_5") (pintype "input"))
    )
    (net (code "148") (name "TDRV5") (class "Default")
      (node (ref "G1") (pin "PA0") (pinfunction "PA0_PA0") (pintype "bidirectional"))
      (node (ref "U6") (pin "12") (pinfunction "+IN_12") (pintype "input"))
      (node (ref "U7") (pin "2") (pinfunction "I_2") (pintype "input"))
    )
    (net (code "149") (name "TDRV6") (class "Default")
      (node (ref "G1") (pin "PA4") (pinfunction "PA4_PA4") (pintype "bidirectional"))
      (node (ref "U6") (pin "3") (pinfunction "+IN_3") (pintype "input"))
      (node (ref "U7") (pin "4") (pinfunction "I_4") (pintype "input"))
    )
    (net (code "150") (name "TDRV7") (class "Default")
      (node (ref "G1") (pin "PC3") (pinfunction "PC3_PC3") (pintype "bidirectional"))
      (node (ref "U5") (pin "4") (pinfunction "I_4") (pintype "input"))
      (node (ref "U6") (pin "10") (pinfunction "+IN_10") (pintype "input"))
    )
    (net (code "151") (name "TDRV8") (class "Default")
      (node (ref "G1") (pin "PC0") (pinfunction "PC0_PC0") (pintype "bidirectional"))
      (node (ref "U5") (pin "2") (pinfunction "I_2") (pintype "input"))
      (node (ref "U6") (pin "5") (pinfunction "+IN_5") (pintype "input"))
    )
    (net (code "152") (name "V+") (class "Default")
      (node (ref "C6") (pin "+") (pinfunction "+_+") (pintype "passive"))
      (node (ref "C7") (pin "1") (pinfunction "1_1") (pintype "passive"))
      (node (ref "G1") (pin "E5V") (pinfunction "E5V_E5V") (pintype "power_in"))
      (node (ref "IC1") (pin "1") (pinfunction "FB_1") (pintype "input"))
      (node (ref "L1") (pin "1") (pinfunction "1_1") (pintype "passive"))
      (node (ref "U2") (pin "3") (pinfunction "FB_3") (pintype "bidirectional"))
    )
    (net (code "153") (name "unconnected-(G1-PadBOOT0)") (class "Default")
      (node (ref "G1") (pin "BOOT0") (pinfunction "BOOT0_BOOT0") (pintype "bidirectional"))
    )
    (net (code "154") (name "unconnected-(G1-PadIOREF2)") (class "Default")
      (node (ref "G1") (pin "IOREF2") (pinfunction "IOREF2_IOREF2") (pintype "input"))
    )
    (net (code "155") (name "unconnected-(G1-PadNC1-PF7)") (class "Default")
      (node (ref "G1") (pin "NC1-PF7") (pinfunction "NC1-PF7_NC1-PF7") (pintype "bidirectional"))
    )
    (net (code "156") (name "unconnected-(G1-PadNC2-PF6)") (class "Default")
      (node (ref "G1") (pin "NC2-PF6") (pinfunction "NC2-PF6_NC2-PF6") (pintype "bidirectional"))
    )
    (net (code "157") (name "unconnected-(G1-PadNC3)") (class "Default")
      (node (ref "G1") (pin "NC3") (pinfunction "NC3_NC3") (pintype "no_connect"))
    )
    (net (code "158") (name "unconnected-(G1-PadNC4)") (class "Default")
      (node (ref "G1") (pin "NC4") (pinfunction "NC4_NC4") (pintype "no_connect"))
    )
    (net (code "159") (name "unconnected-(G1-PadNC5-PD8)") (class "Default")
      (node (ref "G1") (pin "NC5-PD8") (pinfunction "NC5-PD8_NC5-PD8") (pintype "bidirectional"))
    )
    (net (code "160") (name "unconnected-(G1-PadNC6-PB11)") (class "Default")
      (node (ref "G1") (pin "NC6-PB11") (pinfunction "NC6-PB11_NC6-PB11") (pintype "no_connect"))
    )
    (net (code "161") (name "unconnected-(G1-PadNC7-PF5)") (class "Default")
      (node (ref "G1") (pin "NC7-PF5") (pinfunction "NC7-PF5_NC7-PF5") (pintype "bidirectional"))
    )
    (net (code "162") (name "unconnected-(G1-PadNC8-PF4)") (class "Default")
      (node (ref "G1") (pin "NC8-PF4") (pinfunction "NC8-PF4_NC8-PF4") (pintype "bidirectional"))
    )
    (net (code "163") (name "unconnected-(G1-PadNRESET)") (class "Default")
      (node (ref "G1") (pin "NRESET") (pinfunction "NRESET_NRESET") (pintype "input"))
    )
    (net (code "164") (name "unconnected-(G1-PadPA1)") (class "Default")
      (node (ref "G1") (pin "PA1") (pinfunction "PA1_PA1") (pintype "bidirectional"))
    )
    (net (code "165") (name "unconnected-(G1-PadPA2)") (class "Default")
      (node (ref "G1") (pin "PA2") (pinfunction "PA2_PA2") (pintype "bidirectional"))
    )
    (net (code "166") (name "unconnected-(G1-PadPA3)") (class "Default")
      (node (ref "G1") (pin "PA3") (pinfunction "PA3_PA3") (pintype "bidirectional"))
    )
    (net (code "167") (name "unconnected-(G1-PadPA5)") (class "Default")
      (node (ref "G1") (pin "PA5") (pinfunction "PA5_PA5") (pintype "bidirectional"))
    )
    (net (code "168") (name "unconnected-(G1-PadPA7)") (class "Default")
      (node (ref "G1") (pin "PA7") (pinfunction "PA7_PA7") (pintype "bidirectional"))
    )
    (net (code "169") (name "unconnected-(G1-PadPA9)") (class "Default")
      (node (ref "G1") (pin "PA9") (pinfunction "PA9_PA9") (pintype "bidirectional"))
    )
    (net (code "170") (name "unconnected-(G1-PadPA10)") (class "Default")
      (node (ref "G1") (pin "PA10") (pinfunction "PA10_PA10") (pintype "bidirectional"))
    )
    (net (code "171") (name "unconnected-(G1-PadPA11)") (class "Default")
      (node (ref "G1") (pin "PA11") (pinfunction "PA11_PA11") (pintype "bidirectional"))
    )
    (net (code "172") (name "unconnected-(G1-PadPA12)") (class "Default")
      (node (ref "G1") (pin "PA12") (pinfunction "PA12_PA12") (pintype "bidirectional"))
    )
    (net (code "173") (name "unconnected-(G1-PadPA13)") (class "Default")
      (node (ref "G1") (pin "PA13") (pinfunction "PA13_PA13") (pintype "bidirectional"))
    )
    (net (code "174") (name "unconnected-(G1-PadPA14)") (class "Default")
      (node (ref "G1") (pin "PA14") (pinfunction "PA14_PA14") (pintype "bidirectional"))
    )
    (net (code "175") (name "unconnected-(G1-PadPB0)") (class "Default")
      (node (ref "G1") (pin "PB0") (pinfunction "PB0_PB0") (pintype "bidirectional"))
    )
    (net (code "176") (name "unconnected-(G1-PadPC1)") (class "Default")
      (node (ref "G1") (pin "PC1") (pinfunction "PC1_PC1") (pintype "bidirectional"))
    )
    (net (code "177") (name "unconnected-(G1-PadPC4)") (class "Default")
      (node (ref "G1") (pin "PC4") (pinfunction "PC4_PC4") (pintype "bidirectional"))
    )
    (net (code "178") (name "unconnected-(G1-PadPC5)") (class "Default")
      (node (ref "G1") (pin "PC5") (pinfunction "PC5_PC5") (pintype "bidirectional"))
    )
    (net (code "179") (name "unconnected-(G1-PadPC13)") (class "Default")
      (node (ref "G1") (pin "PC13") (pinfunction "PC13_PC13") (pintype "bidirectional"))
    )
    (net (code "180") (name "unconnected-(G1-PadPC14)") (class "Default")
      (node (ref "G1") (pin "PC14") (pinfunction "PC14_PC14") (pintype "bidirectional"))
    )
    (net (code "181") (name "unconnected-(G1-PadPC15)") (class "Default")
      (node (ref "G1") (pin "PC15") (pinfunction "PC15_PC15") (pintype "bidirectional"))
    )
    (net (code "182") (name "unconnected-(G1-PadPF0-PH0)") (class "Default")
      (node (ref "G1") (pin "PF0-PH0") (pinfunction "PF0-PH0_PF0-PH0") (pintype "bidirectional"))
    )
    (net (code "183") (name "unconnected-(H1-MOUNT-PadB3,3)") (class "Default")
      (node (ref "H1") (pin "B3,3") (pinfunction "MOUNT_B3,3") (pintype "passive"))
    )
    (net (code "184") (name "unconnected-(H2-MOUNT-PadB3,3)") (class "Default")
      (node (ref "H2") (pin "B3,3") (pinfunction "MOUNT_B3,3") (pintype "passive"))
    )
    (net (code "185") (name "unconnected-(H3-MOUNT-PadB3,3)") (class "Default")
      (node (ref "H3") (pin "B3,3") (pinfunction "MOUNT_B3,3") (pintype "passive"))
    )
    (net (code "186") (name "unconnected-(H4-MOUNT-PadB3,3)") (class "Default")
      (node (ref "H4") (pin "B3,3") (pinfunction "MOUNT_B3,3") (pintype "passive"))
    )
  )
)
